# SCH_ipm_igbt_module_2025-05-30.net
KiCad netlist of a schematic drawn in EasyEDA
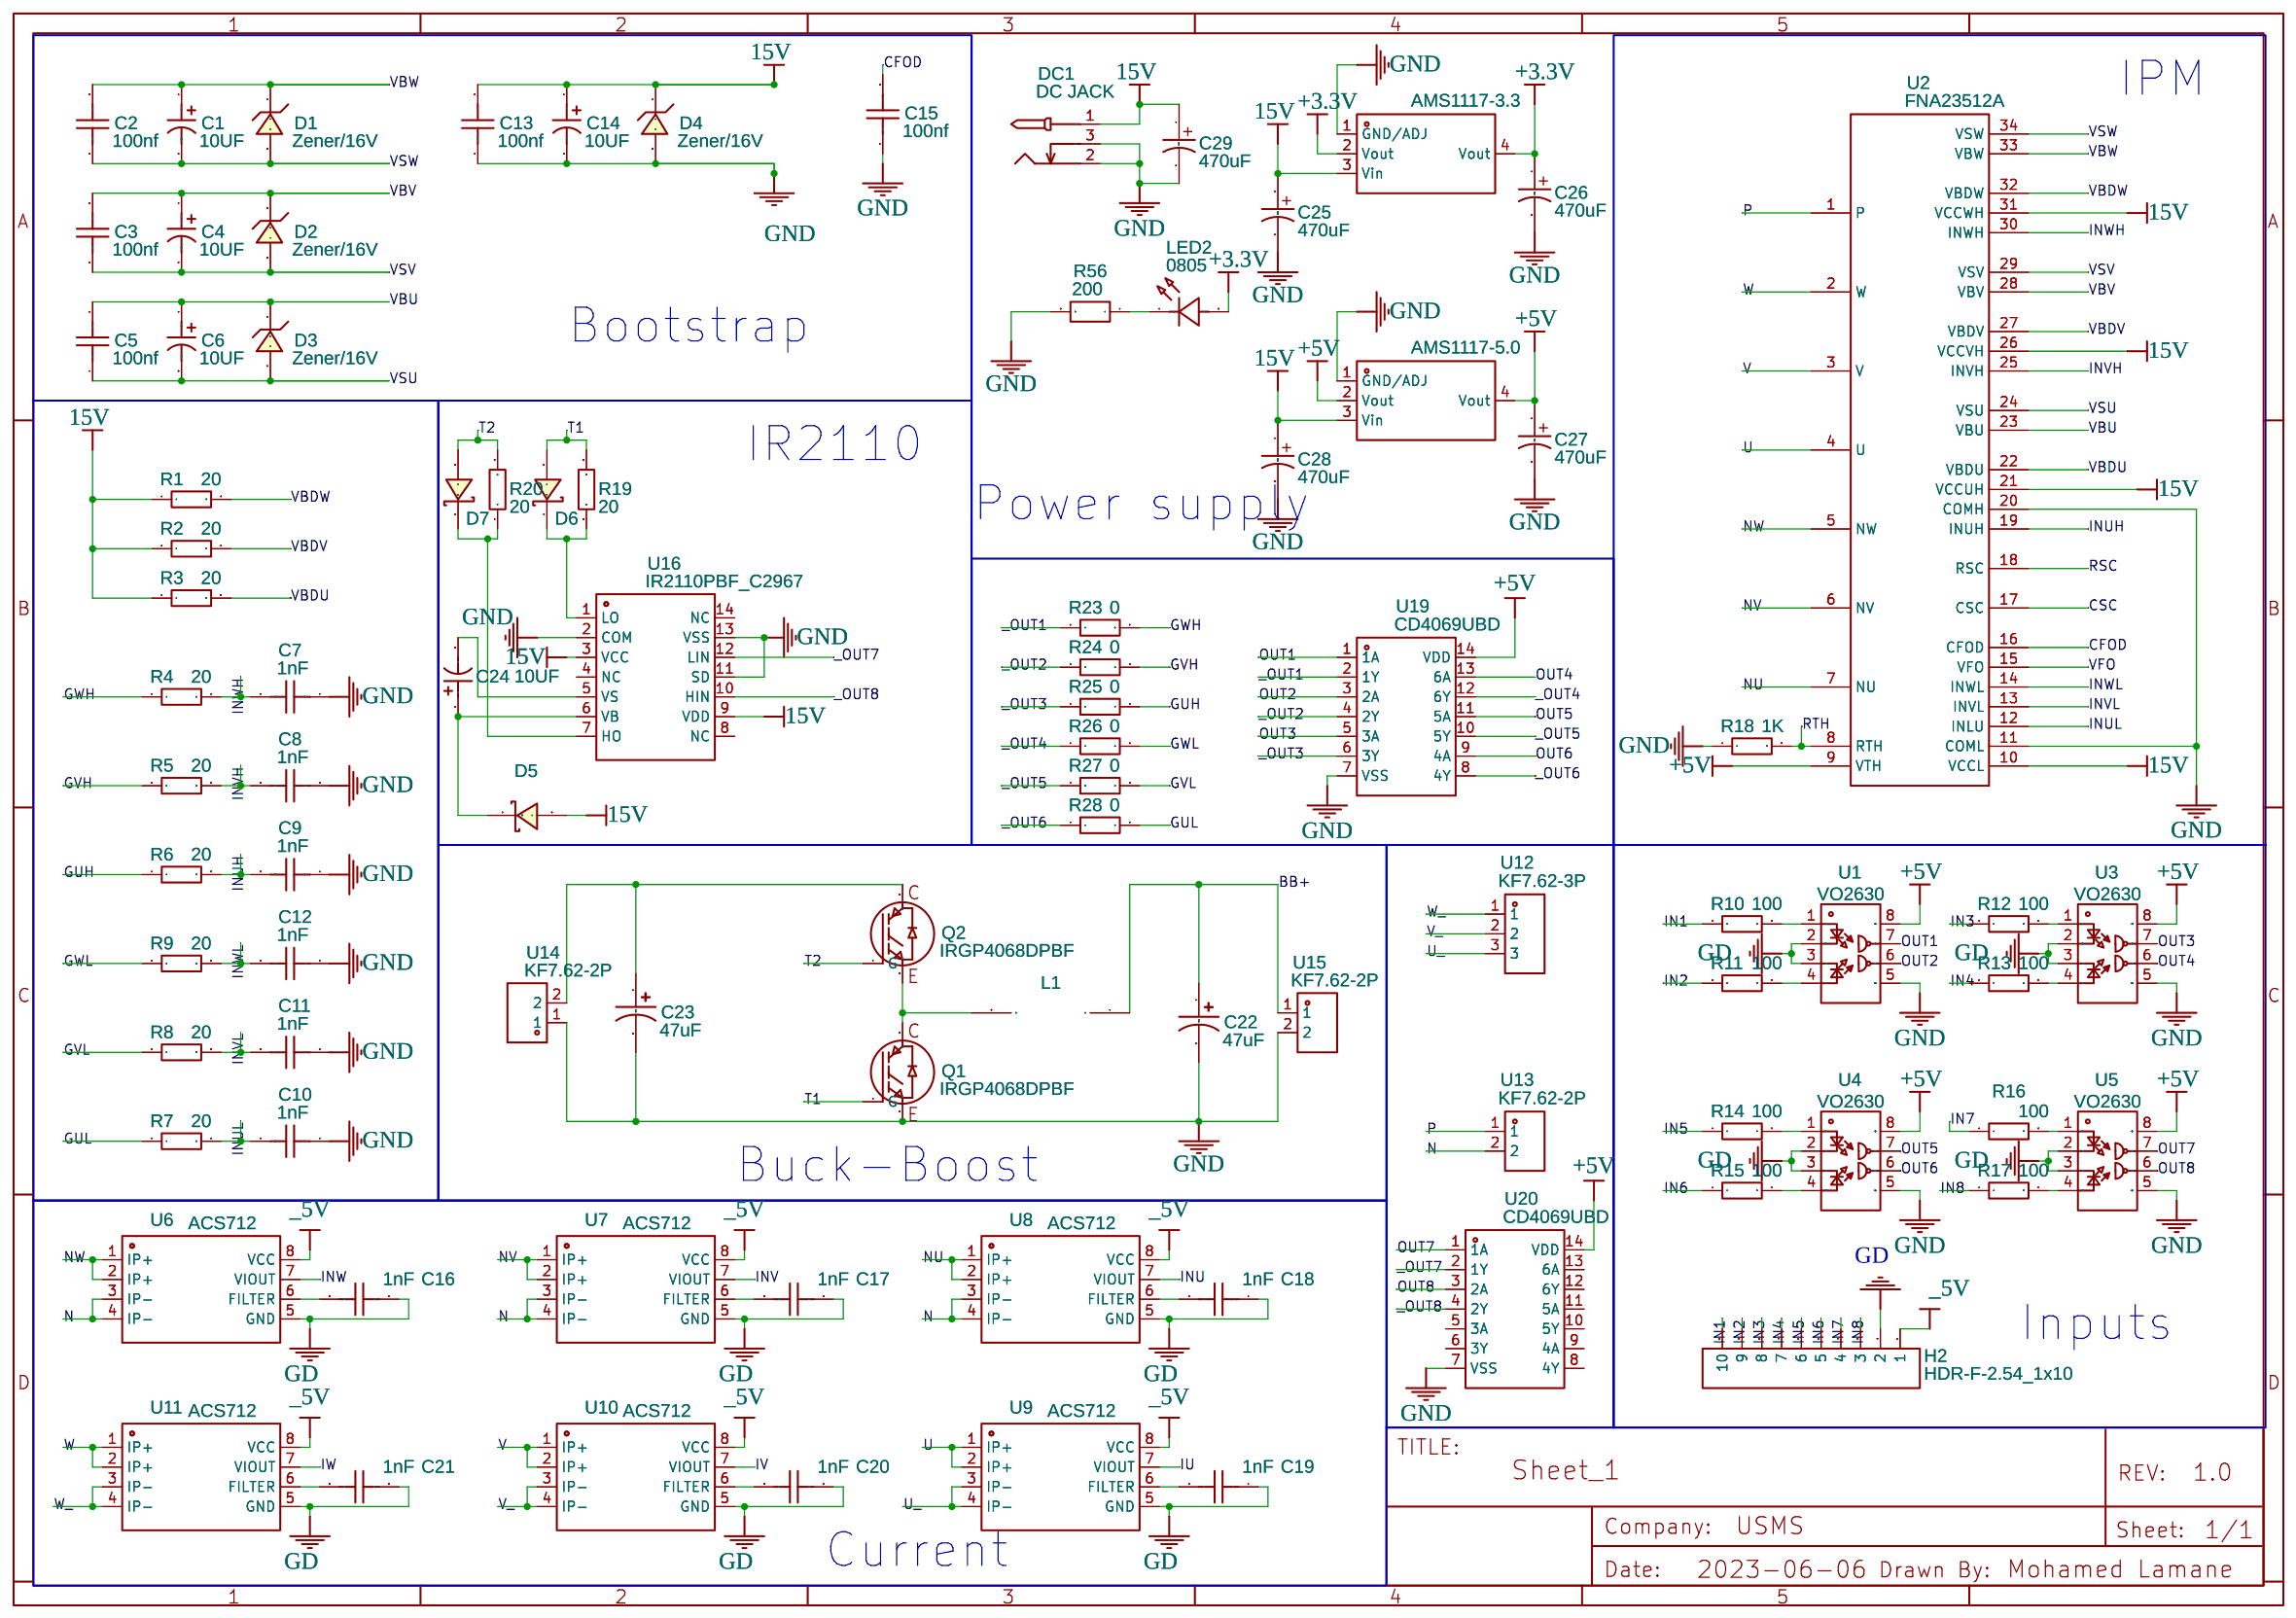
[diagram p0: Sheet_1]
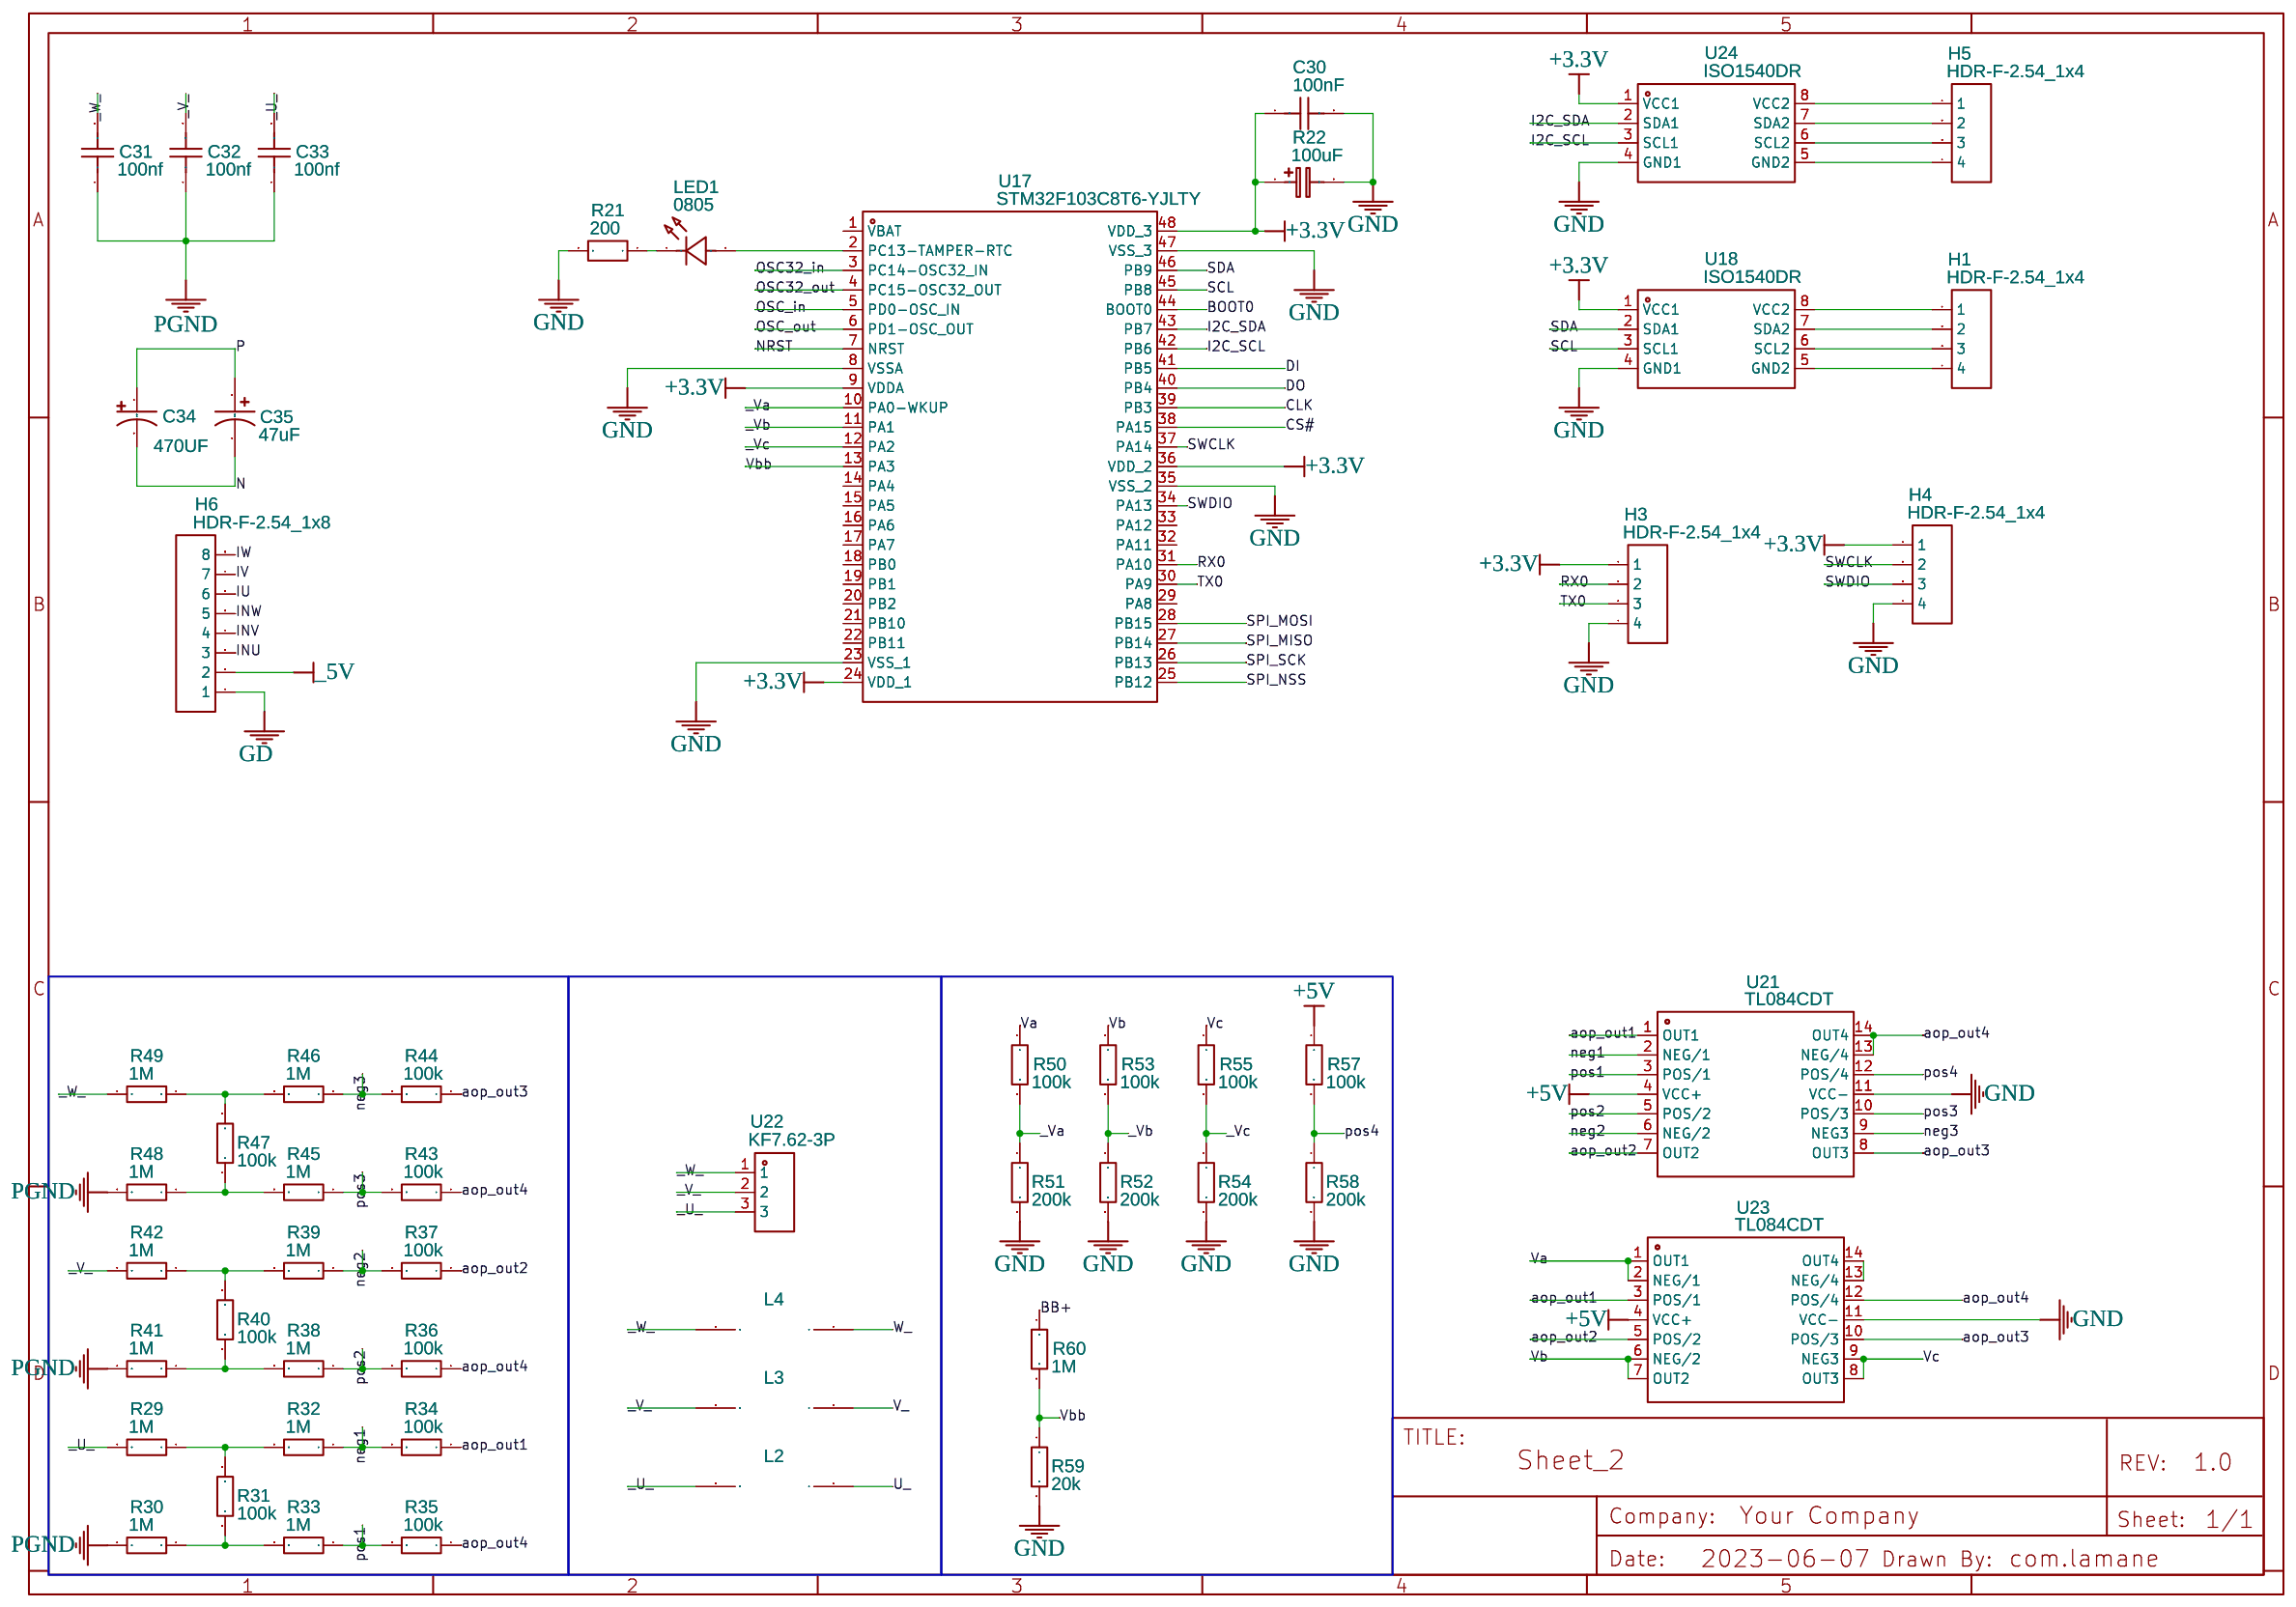
[diagram p1: Sheet_2]

(export (version "E")
  (design (tool "Eeschema 10.0.6"))
  (components
    (comp (ref "C1")
      (value "10UF")
      (fields (field (name "Manufacturer Part") "10uF/25V-C5X11DIP"))
      (libsource (lib "") (part "10UF/25V-C5X11DIP"))
    )
    (comp (ref "C2")
      (value "100nf")
      (fields (field (name "Manufacturer Part") "AC0805KKX7R9BB474"))
      (libsource (lib "") (part "AC0805KKX7R9BB474_1"))
    )
    (comp (ref "C3")
      (value "100nf")
      (fields (field (name "Manufacturer Part") "AC0805KKX7R9BB474"))
      (libsource (lib "") (part "AC0805KKX7R9BB474_1"))
    )
    (comp (ref "C4")
      (value "10UF")
      (fields (field (name "Manufacturer Part") "10uF/25V-C5X11DIP"))
      (libsource (lib "") (part "10UF/25V-C5X11DIP"))
    )
    (comp (ref "C5")
      (value "100nf")
      (fields (field (name "Manufacturer Part") "AC0805KKX7R9BB474"))
      (libsource (lib "") (part "AC0805KKX7R9BB474_1"))
    )
    (comp (ref "C6")
      (value "10UF")
      (fields (field (name "Manufacturer Part") "10uF/25V-C5X11DIP"))
      (libsource (lib "") (part "10UF/25V-C5X11DIP"))
    )
    (comp (ref "C7")
      (value "1nF")
      (fields (field (name "Manufacturer Part") "AC0805KKX7R9BB474"))
      (libsource (lib "") (part "AC0805KKX7R9BB474"))
    )
    (comp (ref "C8")
      (value "1nF")
      (fields (field (name "Manufacturer Part") "AC0805KKX7R9BB474"))
      (libsource (lib "") (part "AC0805KKX7R9BB474"))
    )
    (comp (ref "C9")
      (value "1nF")
      (fields (field (name "Manufacturer Part") "AC0805KKX7R9BB474"))
      (libsource (lib "") (part "AC0805KKX7R9BB474"))
    )
    (comp (ref "C10")
      (value "1nF")
      (fields (field (name "Manufacturer Part") "AC0805KKX7R9BB474"))
      (libsource (lib "") (part "AC0805KKX7R9BB474"))
    )
    (comp (ref "C11")
      (value "1nF")
      (fields (field (name "Manufacturer Part") "AC0805KKX7R9BB474"))
      (libsource (lib "") (part "AC0805KKX7R9BB474"))
    )
    (comp (ref "C12")
      (value "1nF")
      (fields (field (name "Manufacturer Part") "AC0805KKX7R9BB474"))
      (libsource (lib "") (part "AC0805KKX7R9BB474"))
    )
    (comp (ref "C13")
      (value "100nf")
      (fields (field (name "Manufacturer Part") "AC0805KKX7R9BB474"))
      (libsource (lib "") (part "AC0805KKX7R9BB474_1"))
    )
    (comp (ref "C14")
      (value "10UF")
      (fields (field (name "Manufacturer Part") "10uF/25V-C5X11DIP"))
      (libsource (lib "") (part "10UF/25V-C5X11DIP_1"))
    )
    (comp (ref "C15")
      (value "100nf")
      (fields (field (name "Manufacturer Part") "AC0805KKX7R9BB474"))
      (libsource (lib "") (part "AC0805KKX7R9BB474_1"))
    )
    (comp (ref "C16")
      (value "1nF")
      (fields (field (name "Manufacturer Part") "AC0805KKX7R9BB474"))
      (libsource (lib "") (part "AC0805KKX7R9BB474"))
    )
    (comp (ref "C17")
      (value "1nF")
      (fields (field (name "Manufacturer Part") "AC0805KKX7R9BB474"))
      (libsource (lib "") (part "AC0805KKX7R9BB474"))
    )
    (comp (ref "C18")
      (value "1nF")
      (fields (field (name "Manufacturer Part") "AC0805KKX7R9BB474"))
      (libsource (lib "") (part "AC0805KKX7R9BB474"))
    )
    (comp (ref "C19")
      (value "1nF")
      (fields (field (name "Manufacturer Part") "AC0805KKX7R9BB474"))
      (libsource (lib "") (part "AC0805KKX7R9BB474"))
    )
    (comp (ref "C20")
      (value "1nF")
      (fields (field (name "Manufacturer Part") "AC0805KKX7R9BB474"))
      (libsource (lib "") (part "AC0805KKX7R9BB474"))
    )
    (comp (ref "C21")
      (value "1nF")
      (fields (field (name "Manufacturer Part") "AC0805KKX7R9BB474"))
      (libsource (lib "") (part "AC0805KKX7R9BB474"))
    )
    (comp (ref "C22")
      (value "47uF")
      (fields (field (name "Manufacturer Part") "ECG2GM470L26OTBO") (field (name "Manufacturer") "Yunxing"))
      (libsource (lib "") (part "ECG2GM470L26OTBO"))
    )
    (comp (ref "C23")
      (value "47uF")
      (fields (field (name "Manufacturer Part") "ECG2GM470L26OTBO") (field (name "Manufacturer") "Yunxing"))
      (libsource (lib "") (part "ECG2GM470L26OTBO"))
    )
    (comp (ref "C24")
      (value "10UF")
      (fields (field (name "Manufacturer Part") "10uF/25V-C5X11DIP"))
      (libsource (lib "") (part "10UF/25V-C5X11DIP_2"))
    )
    (comp (ref "C25")
      (value "470uF")
      (fields (field (name "Manufacturer Part") "EEEFK1A471GP") (field (name "Manufacturer") "PANASONIC"))
      (libsource (lib "") (part "EEEFK1A471GP"))
    )
    (comp (ref "C26")
      (value "470uF")
      (fields (field (name "Manufacturer Part") "EEEFK1A471GP") (field (name "Manufacturer") "PANASONIC"))
      (libsource (lib "") (part "EEEFK1A471GP"))
    )
    (comp (ref "C27")
      (value "470uF")
      (fields (field (name "Manufacturer Part") "EEEFK1A471GP") (field (name "Manufacturer") "PANASONIC"))
      (libsource (lib "") (part "EEEFK1A471GP"))
    )
    (comp (ref "C28")
      (value "470uF")
      (fields (field (name "Manufacturer Part") "EEEFK1A471GP") (field (name "Manufacturer") "PANASONIC"))
      (libsource (lib "") (part "EEEFK1A471GP"))
    )
    (comp (ref "C29")
      (value "470uF")
      (fields (field (name "Manufacturer Part") "EEEFK1A471GP") (field (name "Manufacturer") "PANASONIC"))
      (libsource (lib "") (part "EEEFK1A471GP"))
    )
    (comp (ref "D1")
      (value "Zener/16V")
      (fields (field (name "Manufacturer Part") "MM3Z10VST1G") (field (name "Manufacturer") "onsemi(安森美)"))
      (libsource (lib "") (part "MM3Z10VST1G"))
    )
    (comp (ref "D2")
      (value "Zener/16V")
      (fields (field (name "Manufacturer Part") "MM3Z10VST1G") (field (name "Manufacturer") "onsemi(安森美)"))
      (libsource (lib "") (part "MM3Z10VST1G"))
    )
    (comp (ref "D3")
      (value "Zener/16V")
      (fields (field (name "Manufacturer Part") "MM3Z10VST1G") (field (name "Manufacturer") "onsemi(安森美)"))
      (libsource (lib "") (part "MM3Z10VST1G"))
    )
    (comp (ref "D4")
      (value "Zener/16V")
      (fields (field (name "Manufacturer Part") "MM3Z10VST1G") (field (name "Manufacturer") "onsemi(安森美)"))
      (libsource (lib "") (part "MM3Z10VST1G"))
    )
    (comp (ref "D5") (value "SODFL250X10-2N") (libsource (lib "") (part "SODFL250X10-2N_1")))
    (comp (ref "D6") (value "SODFL250X10-2N") (libsource (lib "") (part "SODFL250X10-2N")))
    (comp (ref "D7") (value "SODFL250X10-2N") (libsource (lib "") (part "SODFL250X10-2N")))
    (comp (ref "DC1")
      (value "DC JACK")
      (fields (field (name "Manufacturer Part") "DC005-2.0MM") (field (name "Manufacturer") "SOFNG"))
      (libsource (lib "") (part "DC JACK"))
    )
    (comp (ref "H2") (value "HDR-F-2.54_1x10") (libsource (lib "") (part "HDR-F-2.54_1x10")))
    (comp (ref "L1") (value "indu") (libsource (lib "") (part "indu")))
    (comp (ref "LED2")
      (value "0805")
      (fields (field (name "Manufacturer Part") "D21121000251-LED0805_R"))
      (libsource (lib "") (part "D21121000251-LED0805_R"))
    )
    (comp (ref "NO1")
      (value "AMS1117-3.3")
      (fields (field (name "Manufacturer Part") "AMS1117-3.3-YJLTY"))
      (libsource (lib "") (part "AMS1117-3.3-YJLTY"))
    )
    (comp (ref "NO2")
      (value "AMS1117-5.0")
      (fields (field (name "Manufacturer Part") "AMS1117-3.3-YJLTY"))
      (libsource (lib "") (part "AMS1117-3.3-YJLTY"))
    )
    (comp (ref "Q1")
      (value "IRGP4068DPBF")
      (fields (field (name "Manufacturer") "IR"))
      (libsource (lib "") (part "IRGP4068DPBF"))
    )
    (comp (ref "Q2")
      (value "IRGP4068DPBF")
      (fields (field (name "Manufacturer") "IR"))
      (libsource (lib "") (part "IRGP4068DPBF"))
    )
    (comp (ref "R1")
      (value "20")
      (fields (field (name "Manufacturer Part") "8K1%-R0603"))
      (libsource (lib "") (part "8K1%-R0603"))
    )
    (comp (ref "R2")
      (value "20")
      (fields (field (name "Manufacturer Part") "8K1%-R0603"))
      (libsource (lib "") (part "8K1%-R0603"))
    )
    (comp (ref "R3")
      (value "20")
      (fields (field (name "Manufacturer Part") "8K1%-R0603"))
      (libsource (lib "") (part "8K1%-R0603"))
    )
    (comp (ref "R4")
      (value "20")
      (fields (field (name "Manufacturer Part") "8K1%-R0603"))
      (libsource (lib "") (part "8K1%-R0603"))
    )
    (comp (ref "R5")
      (value "20")
      (fields (field (name "Manufacturer Part") "8K1%-R0603"))
      (libsource (lib "") (part "8K1%-R0603"))
    )
    (comp (ref "R6")
      (value "20")
      (fields (field (name "Manufacturer Part") "8K1%-R0603"))
      (libsource (lib "") (part "8K1%-R0603"))
    )
    (comp (ref "R7")
      (value "20")
      (fields (field (name "Manufacturer Part") "8K1%-R0603"))
      (libsource (lib "") (part "8K1%-R0603"))
    )
    (comp (ref "R8")
      (value "20")
      (fields (field (name "Manufacturer Part") "8K1%-R0603"))
      (libsource (lib "") (part "8K1%-R0603"))
    )
    (comp (ref "R9")
      (value "20")
      (fields (field (name "Manufacturer Part") "8K1%-R0603"))
      (libsource (lib "") (part "8K1%-R0603"))
    )
    (comp (ref "R10")
      (value "100")
      (fields (field (name "Manufacturer Part") "8K1%-R0603"))
      (libsource (lib "") (part "8K1%-R0603"))
    )
    (comp (ref "R11")
      (value "100")
      (fields (field (name "Manufacturer Part") "8K1%-R0603"))
      (libsource (lib "") (part "8K1%-R0603"))
    )
    (comp (ref "R12")
      (value "100")
      (fields (field (name "Manufacturer Part") "8K1%-R0603"))
      (libsource (lib "") (part "8K1%-R0603"))
    )
    (comp (ref "R13")
      (value "100")
      (fields (field (name "Manufacturer Part") "8K1%-R0603"))
      (libsource (lib "") (part "8K1%-R0603"))
    )
    (comp (ref "R14")
      (value "100")
      (fields (field (name "Manufacturer Part") "8K1%-R0603"))
      (libsource (lib "") (part "8K1%-R0603"))
    )
    (comp (ref "R15")
      (value "100")
      (fields (field (name "Manufacturer Part") "8K1%-R0603"))
      (libsource (lib "") (part "8K1%-R0603"))
    )
    (comp (ref "R16")
      (value "100")
      (fields (field (name "Manufacturer Part") "8K1%-R0603"))
      (libsource (lib "") (part "8K1%-R0603"))
    )
    (comp (ref "R17")
      (value "100")
      (fields (field (name "Manufacturer Part") "8K1%-R0603"))
      (libsource (lib "") (part "8K1%-R0603"))
    )
    (comp (ref "R18")
      (value "1K")
      (fields (field (name "Manufacturer Part") "8K1%-R0603"))
      (libsource (lib "") (part "8K1%-R0603"))
    )
    (comp (ref "R19")
      (value "20")
      (fields (field (name "Manufacturer Part") "8K1%-R0603"))
      (libsource (lib "") (part "8K1%-R0603_1"))
    )
    (comp (ref "R20")
      (value "20")
      (fields (field (name "Manufacturer Part") "8K1%-R0603"))
      (libsource (lib "") (part "8K1%-R0603_1"))
    )
    (comp (ref "R23")
      (value "0")
      (fields (field (name "Manufacturer Part") "8K1%-R0603"))
      (libsource (lib "") (part "8K1%-R0603"))
    )
    (comp (ref "R24")
      (value "0")
      (fields (field (name "Manufacturer Part") "8K1%-R0603"))
      (libsource (lib "") (part "8K1%-R0603"))
    )
    (comp (ref "R25")
      (value "0")
      (fields (field (name "Manufacturer Part") "8K1%-R0603"))
      (libsource (lib "") (part "8K1%-R0603"))
    )
    (comp (ref "R26")
      (value "0")
      (fields (field (name "Manufacturer Part") "8K1%-R0603"))
      (libsource (lib "") (part "8K1%-R0603"))
    )
    (comp (ref "R27")
      (value "0")
      (fields (field (name "Manufacturer Part") "8K1%-R0603"))
      (libsource (lib "") (part "8K1%-R0603"))
    )
    (comp (ref "R28")
      (value "0")
      (fields (field (name "Manufacturer Part") "8K1%-R0603"))
      (libsource (lib "") (part "8K1%-R0603"))
    )
    (comp (ref "R56")
      (value "200")
      (fields (field (name "Manufacturer Part") "PTFR0805B9K10P9") (field (name "Manufacturer") "RESI(开步睿思）"))
      (libsource (lib "") (part "PTFR0805B9K10P9"))
    )
    (comp (ref "U1")
      (value "VO2630")
      (fields (field (name "Manufacturer Part") "VO2630-X007T") (field (name "Manufacturer") "VISHAY(威世)"))
      (libsource (lib "") (part "VO2630-X007T"))
    )
    (comp (ref "U2")
      (value "FNA23512A")
      (fields (field (name "Manufacturer") "ON(安森美)"))
      (libsource (lib "") (part "FNA23512A"))
    )
    (comp (ref "U3")
      (value "VO2630")
      (fields (field (name "Manufacturer Part") "VO2630-X007T") (field (name "Manufacturer") "VISHAY(威世)"))
      (libsource (lib "") (part "VO2630-X007T"))
    )
    (comp (ref "U4")
      (value "VO2630")
      (fields (field (name "Manufacturer Part") "VO2630-X007T") (field (name "Manufacturer") "VISHAY(威世)"))
      (libsource (lib "") (part "VO2630-X007T"))
    )
    (comp (ref "U5")
      (value "VO2630")
      (fields (field (name "Manufacturer Part") "VO2630-X007T") (field (name "Manufacturer") "VISHAY(威世)"))
      (libsource (lib "") (part "VO2630-X007T"))
    )
    (comp (ref "U6")
      (value "ACS712")
      (fields
        (field (name "Manufacturer Part") "ACS712ELCTR-30A-T")
        (field (name "Manufacturer") "ALLEGRO(美国埃戈罗)")
      )
      (libsource (lib "") (part "ACS712ELCTR-30A-T"))
    )
    (comp (ref "U7")
      (value "ACS712")
      (fields
        (field (name "Manufacturer Part") "ACS712ELCTR-30A-T")
        (field (name "Manufacturer") "ALLEGRO(美国埃戈罗)")
      )
      (libsource (lib "") (part "ACS712ELCTR-30A-T"))
    )
    (comp (ref "U8")
      (value "ACS712")
      (fields
        (field (name "Manufacturer Part") "ACS712ELCTR-30A-T")
        (field (name "Manufacturer") "ALLEGRO(美国埃戈罗)")
      )
      (libsource (lib "") (part "ACS712ELCTR-30A-T"))
    )
    (comp (ref "U9")
      (value "ACS712")
      (fields
        (field (name "Manufacturer Part") "ACS712ELCTR-30A-T")
        (field (name "Manufacturer") "ALLEGRO(美国埃戈罗)")
      )
      (libsource (lib "") (part "ACS712ELCTR-30A-T"))
    )
    (comp (ref "U10")
      (value "ACS712")
      (fields
        (field (name "Manufacturer Part") "ACS712ELCTR-30A-T")
        (field (name "Manufacturer") "ALLEGRO(美国埃戈罗)")
      )
      (libsource (lib "") (part "ACS712ELCTR-30A-T"))
    )
    (comp (ref "U11")
      (value "ACS712")
      (fields
        (field (name "Manufacturer Part") "ACS712ELCTR-30A-T")
        (field (name "Manufacturer") "ALLEGRO(美国埃戈罗)")
      )
      (libsource (lib "") (part "ACS712ELCTR-30A-T"))
    )
    (comp (ref "U12")
      (value "KF7.62-3P")
      (fields (field (name "Manufacturer") "KEFA(科发)"))
      (libsource (lib "") (part "KF7.62-3P"))
    )
    (comp (ref "U13")
      (value "KF7.62-2P")
      (fields (field (name "Manufacturer") "KEFA(科发)"))
      (libsource (lib "") (part "KF7.62-2P"))
    )
    (comp (ref "U14")
      (value "KF7.62-2P")
      (fields (field (name "Manufacturer") "KEFA(科发)"))
      (libsource (lib "") (part "KF7.62-2P_1"))
    )
    (comp (ref "U15")
      (value "KF7.62-2P")
      (fields (field (name "Manufacturer") "KEFA(科发)"))
      (libsource (lib "") (part "KF7.62-2P"))
    )
    (comp (ref "U16")
      (value "IR2110PBF_C2967")
      (fields (field (name "Manufacturer Part") "IR2110PBF") (field (name "Manufacturer") "Infineon(英飞凌)"))
      (libsource (lib "") (part "IR2110PBF_C2967"))
    )
    (comp (ref "U19")
      (value "CD4069UBD")
      (fields (field (name "Manufacturer") "HTC"))
      (libsource (lib "") (part "CD4069UBD"))
    )
    (comp (ref "U20")
      (value "CD4069UBD")
      (fields (field (name "Manufacturer") "HTC"))
      (libsource (lib "") (part "CD4069UBD"))
    )
    (comp (ref "C30")
      (value "100nF")
      (fields (field (name "Manufacturer Part") "GRM216R71H103KA01D") (field (name "Manufacturer") "MuRata"))
      (libsource (lib "") (part "GRM216R71H103KA01D"))
    )
    (comp (ref "C31")
      (value "100nf")
      (fields
        (field (name "Manufacturer Part") "1uf/250V/CBBCapacitor")
        (field (name "Manufacturer") "ReliaPro")
      )
      (libsource (lib "") (part "1uf/250V/CBBCapacitor"))
    )
    (comp (ref "C32")
      (value "100nf")
      (fields
        (field (name "Manufacturer Part") "1uf/250V/CBBCapacitor")
        (field (name "Manufacturer") "ReliaPro")
      )
      (libsource (lib "") (part "1uf/250V/CBBCapacitor"))
    )
    (comp (ref "C33")
      (value "100nf")
      (fields
        (field (name "Manufacturer Part") "1uf/250V/CBBCapacitor")
        (field (name "Manufacturer") "ReliaPro")
      )
      (libsource (lib "") (part "1uf/250V/CBBCapacitor"))
    )
    (comp (ref "C34") (value "470UF") (libsource (lib "") (part "407UF/400V")))
    (comp (ref "C35")
      (value "47uF")
      (fields (field (name "Manufacturer Part") "ECG2GM470L26OTBO") (field (name "Manufacturer") "Yunxing"))
      (libsource (lib "") (part "ECG2GM470L26OTBO"))
    )
    (comp (ref "H1") (value "HDR-F-2.54_1x4") (libsource (lib "") (part "HDR-F-2.54_1x4")))
    (comp (ref "H3") (value "HDR-F-2.54_1x4") (libsource (lib "") (part "HDR-F-2.54_1x4")))
    (comp (ref "H4") (value "HDR-F-2.54_1x4") (libsource (lib "") (part "HDR-F-2.54_1x4")))
    (comp (ref "H5") (value "HDR-F-2.54_1x4") (libsource (lib "") (part "HDR-F-2.54_1x4")))
    (comp (ref "H6") (value "HDR-F-2.54_1x8") (libsource (lib "") (part "HDR-F-2.54_1x8")))
    (comp (ref "L2") (value "indu") (libsource (lib "") (part "indu")))
    (comp (ref "L3") (value "indu") (libsource (lib "") (part "indu")))
    (comp (ref "L4") (value "indu") (libsource (lib "") (part "indu")))
    (comp (ref "LED1")
      (value "0805")
      (fields (field (name "Manufacturer Part") "D21121000251-LED0805_R"))
      (libsource (lib "") (part "D21121000251-LED0805_R"))
    )
    (comp (ref "R21")
      (value "200")
      (fields (field (name "Manufacturer Part") "PTFR0805B9K10P9") (field (name "Manufacturer") "RESI(开步睿思）"))
      (libsource (lib "") (part "PTFR0805B9K10P9"))
    )
    (comp (ref "R22")
      (value "100uF")
      (fields
        (field (name "Manufacturer Part") "T520A107M006ATE045")
        (field (name "Manufacturer") "KEMET(基美)")
      )
      (libsource (lib "") (part "T520A107M006ATE045"))
    )
    (comp (ref "R29")
      (value "1M")
      (fields (field (name "Manufacturer Part") "8K1%-R0603"))
      (libsource (lib "") (part "8K1%-R0603"))
    )
    (comp (ref "R30")
      (value "1M")
      (fields (field (name "Manufacturer Part") "8K1%-R0603"))
      (libsource (lib "") (part "8K1%-R0603"))
    )
    (comp (ref "R31")
      (value "100k")
      (fields (field (name "Manufacturer Part") "8K1%-R0603"))
      (libsource (lib "") (part "8K1%-R0603_2"))
    )
    (comp (ref "R32")
      (value "1M")
      (fields (field (name "Manufacturer Part") "8K1%-R0603"))
      (libsource (lib "") (part "8K1%-R0603"))
    )
    (comp (ref "R33")
      (value "1M")
      (fields (field (name "Manufacturer Part") "8K1%-R0603"))
      (libsource (lib "") (part "8K1%-R0603"))
    )
    (comp (ref "R34")
      (value "100k")
      (fields (field (name "Manufacturer Part") "8K1%-R0603"))
      (libsource (lib "") (part "8K1%-R0603"))
    )
    (comp (ref "R35")
      (value "100k")
      (fields (field (name "Manufacturer Part") "8K1%-R0603"))
      (libsource (lib "") (part "8K1%-R0603"))
    )
    (comp (ref "R36")
      (value "100k")
      (fields (field (name "Manufacturer Part") "8K1%-R0603"))
      (libsource (lib "") (part "8K1%-R0603"))
    )
    (comp (ref "R37")
      (value "100k")
      (fields (field (name "Manufacturer Part") "8K1%-R0603"))
      (libsource (lib "") (part "8K1%-R0603"))
    )
    (comp (ref "R38")
      (value "1M")
      (fields (field (name "Manufacturer Part") "8K1%-R0603"))
      (libsource (lib "") (part "8K1%-R0603"))
    )
    (comp (ref "R39")
      (value "1M")
      (fields (field (name "Manufacturer Part") "8K1%-R0603"))
      (libsource (lib "") (part "8K1%-R0603"))
    )
    (comp (ref "R40")
      (value "100k")
      (fields (field (name "Manufacturer Part") "8K1%-R0603"))
      (libsource (lib "") (part "8K1%-R0603_2"))
    )
    (comp (ref "R41")
      (value "1M")
      (fields (field (name "Manufacturer Part") "8K1%-R0603"))
      (libsource (lib "") (part "8K1%-R0603"))
    )
    (comp (ref "R42")
      (value "1M")
      (fields (field (name "Manufacturer Part") "8K1%-R0603"))
      (libsource (lib "") (part "8K1%-R0603"))
    )
    (comp (ref "R43")
      (value "100k")
      (fields (field (name "Manufacturer Part") "8K1%-R0603"))
      (libsource (lib "") (part "8K1%-R0603"))
    )
    (comp (ref "R44")
      (value "100k")
      (fields (field (name "Manufacturer Part") "8K1%-R0603"))
      (libsource (lib "") (part "8K1%-R0603"))
    )
    (comp (ref "R45")
      (value "1M")
      (fields (field (name "Manufacturer Part") "8K1%-R0603"))
      (libsource (lib "") (part "8K1%-R0603"))
    )
    (comp (ref "R46")
      (value "1M")
      (fields (field (name "Manufacturer Part") "8K1%-R0603"))
      (libsource (lib "") (part "8K1%-R0603"))
    )
    (comp (ref "R47")
      (value "100k")
      (fields (field (name "Manufacturer Part") "8K1%-R0603"))
      (libsource (lib "") (part "8K1%-R0603_2"))
    )
    (comp (ref "R48")
      (value "1M")
      (fields (field (name "Manufacturer Part") "8K1%-R0603"))
      (libsource (lib "") (part "8K1%-R0603"))
    )
    (comp (ref "R49")
      (value "1M")
      (fields (field (name "Manufacturer Part") "8K1%-R0603"))
      (libsource (lib "") (part "8K1%-R0603"))
    )
    (comp (ref "R50")
      (value "100k")
      (fields (field (name "Manufacturer Part") "8K1%-R0603"))
      (libsource (lib "") (part "8K1%-R0603_1"))
    )
    (comp (ref "R51")
      (value "200k")
      (fields (field (name "Manufacturer Part") "8K1%-R0603"))
      (libsource (lib "") (part "8K1%-R0603_1"))
    )
    (comp (ref "R52")
      (value "200k")
      (fields (field (name "Manufacturer Part") "8K1%-R0603"))
      (libsource (lib "") (part "8K1%-R0603_1"))
    )
    (comp (ref "R53")
      (value "100k")
      (fields (field (name "Manufacturer Part") "8K1%-R0603"))
      (libsource (lib "") (part "8K1%-R0603_1"))
    )
    (comp (ref "R54")
      (value "200k")
      (fields (field (name "Manufacturer Part") "8K1%-R0603"))
      (libsource (lib "") (part "8K1%-R0603_1"))
    )
    (comp (ref "R55")
      (value "100k")
      (fields (field (name "Manufacturer Part") "8K1%-R0603"))
      (libsource (lib "") (part "8K1%-R0603_1"))
    )
    (comp (ref "R57")
      (value "100k")
      (fields (field (name "Manufacturer Part") "8K1%-R0603"))
      (libsource (lib "") (part "8K1%-R0603_1"))
    )
    (comp (ref "R58")
      (value "200k")
      (fields (field (name "Manufacturer Part") "8K1%-R0603"))
      (libsource (lib "") (part "8K1%-R0603_1"))
    )
    (comp (ref "R59")
      (value "20k")
      (fields (field (name "Manufacturer Part") "8K1%-R0603"))
      (libsource (lib "") (part "8K1%-R0603_1"))
    )
    (comp (ref "R60")
      (value "1M")
      (fields (field (name "Manufacturer Part") "8K1%-R0603"))
      (libsource (lib "") (part "8K1%-R0603_1"))
    )
    (comp (ref "U17") (value "STM32F103C8T6-YJLTY") (libsource (lib "") (part "STM32F103C8T6-YJLTY")))
    (comp (ref "U18")
      (value "ISO1540DR")
      (fields (field (name "Manufacturer") "TI(德州仪器)"))
      (libsource (lib "") (part "ISO1540DR"))
    )
    (comp (ref "U21")
      (value "TL084CDT")
      (fields (field (name "Manufacturer") "ST(意法半导体)"))
      (libsource (lib "") (part "TL084CDT"))
    )
    (comp (ref "U22")
      (value "KF7.62-3P")
      (fields (field (name "Manufacturer") "KEFA(科发)"))
      (libsource (lib "") (part "KF7.62-3P"))
    )
    (comp (ref "U23")
      (value "TL084CDT")
      (fields (field (name "Manufacturer") "ST(意法半导体)"))
      (libsource (lib "") (part "TL084CDT"))
    )
    (comp (ref "U24")
      (value "ISO1540DR")
      (fields (field (name "Manufacturer") "TI(德州仪器)"))
      (libsource (lib "") (part "ISO1540DR"))
    )
  )
  (nets
    (net (code "1") (name "+3.3V") (class "Default")
      (node (ref "C26") (pin "1") (pinfunction "1_1") (pintype "unspecified"))
      (node (ref "C30") (pin "1") (pinfunction "1_1") (pintype "unspecified"))
      (node (ref "H3") (pin "1") (pinfunction "1_1") (pintype "unspecified"))
      (node (ref "H4") (pin "1") (pinfunction "1_1") (pintype "unspecified"))
      (node (ref "LED2") (pin "2") (pinfunction "A_2") (pintype "unspecified"))
      (node (ref "NO1") (pin "2") (pinfunction "Vout_2") (pintype "unspecified"))
      (node (ref "NO1") (pin "4") (pinfunction "Vout_4") (pintype "unspecified"))
      (node (ref "R22") (pin "1") (pinfunction "1_1") (pintype "unspecified"))
      (node (ref "U17") (pin "24") (pinfunction "VDD_1_24") (pintype "unspecified"))
      (node (ref "U17") (pin "36") (pinfunction "VDD_2_36") (pintype "unspecified"))
      (node (ref "U17") (pin "48") (pinfunction "VDD_3_48") (pintype "unspecified"))
      (node (ref "U17") (pin "9") (pinfunction "VDDA_9") (pintype "unspecified"))
      (node (ref "U18") (pin "1") (pinfunction "VCC1_1") (pintype "unspecified"))
      (node (ref "U24") (pin "1") (pinfunction "VCC1_1") (pintype "unspecified"))
    )
    (net (code "2") (name "+5V") (class "Default")
      (node (ref "C27") (pin "1") (pinfunction "1_1") (pintype "unspecified"))
      (node (ref "NO2") (pin "2") (pinfunction "Vout_2") (pintype "unspecified"))
      (node (ref "NO2") (pin "4") (pinfunction "Vout_4") (pintype "unspecified"))
      (node (ref "R57") (pin "1") (pinfunction "1_1") (pintype "unspecified"))
      (node (ref "U1") (pin "8") (pinfunction "VCC_8") (pintype "unspecified"))
      (node (ref "U19") (pin "14") (pinfunction "VDD_14") (pintype "unspecified"))
      (node (ref "U2") (pin "9") (pinfunction "VTH_9") (pintype "unspecified"))
      (node (ref "U20") (pin "14") (pinfunction "VDD_14") (pintype "unspecified"))
      (node (ref "U21") (pin "4") (pinfunction "VCC+_4") (pintype "unspecified"))
      (node (ref "U23") (pin "4") (pinfunction "VCC+_4") (pintype "unspecified"))
      (node (ref "U3") (pin "8") (pinfunction "VCC_8") (pintype "unspecified"))
      (node (ref "U4") (pin "8") (pinfunction "VCC_8") (pintype "unspecified"))
      (node (ref "U5") (pin "8") (pinfunction "VCC_8") (pintype "unspecified"))
    )
    (net (code "3") (name "15V") (class "Default")
      (node (ref "C13") (pin "2") (pinfunction "2_2") (pintype "unspecified"))
      (node (ref "C14") (pin "1") (pinfunction "1_1") (pintype "input"))
      (node (ref "C25") (pin "1") (pinfunction "1_1") (pintype "unspecified"))
      (node (ref "C28") (pin "1") (pinfunction "1_1") (pintype "unspecified"))
      (node (ref "C29") (pin "1") (pinfunction "1_1") (pintype "unspecified"))
      (node (ref "D4") (pin "1") (pinfunction "K_1") (pintype "unspecified"))
      (node (ref "D5") (pin "2") (pinfunction "A_2") (pintype "unspecified"))
      (node (ref "DC1") (pin "1") (pinfunction "1_1") (pintype "unspecified"))
      (node (ref "NO1") (pin "3") (pinfunction "Vin_3") (pintype "unspecified"))
      (node (ref "NO2") (pin "3") (pinfunction "Vin_3") (pintype "unspecified"))
      (node (ref "R1") (pin "1") (pinfunction "1_1") (pintype "unspecified"))
      (node (ref "R2") (pin "1") (pinfunction "1_1") (pintype "unspecified"))
      (node (ref "R3") (pin "1") (pinfunction "1_1") (pintype "unspecified"))
      (node (ref "U16") (pin "3") (pinfunction "VCC_3") (pintype "unspecified"))
      (node (ref "U16") (pin "9") (pinfunction "VDD_9") (pintype "unspecified"))
      (node (ref "U2") (pin "10") (pinfunction "VCCL_10") (pintype "unspecified"))
      (node (ref "U2") (pin "21") (pinfunction "VCCUH_21") (pintype "unspecified"))
      (node (ref "U2") (pin "26") (pinfunction "VCCVH_26") (pintype "unspecified"))
      (node (ref "U2") (pin "31") (pinfunction "VCCWH_31") (pintype "unspecified"))
    )
    (net (code "4") (name "BB+") (class "Default")
      (node (ref "C22") (pin "1") (pinfunction "1_1") (pintype "unspecified"))
      (node (ref "L1") (pin "1") (pinfunction "1_1") (pintype "unspecified"))
      (node (ref "R60") (pin "1") (pinfunction "1_1") (pintype "unspecified"))
      (node (ref "U15") (pin "1") (pinfunction "1_1") (pintype "unspecified"))
    )
    (net (code "5") (name "BOOT0") (class "Default")
      (node (ref "U17") (pin "44") (pinfunction "BOOT0_44") (pintype "unspecified"))
    )
    (net (code "6") (name "CFOD") (class "Default")
      (node (ref "C15") (pin "2") (pinfunction "2_2") (pintype "unspecified"))
      (node (ref "U2") (pin "16") (pinfunction "CFOD_16") (pintype "unspecified"))
    )
    (net (code "7") (name "CLK") (class "Default")
      (node (ref "U17") (pin "39") (pinfunction "PB3_39") (pintype "unspecified"))
    )
    (net (code "8") (name "CS#") (class "Default")
      (node (ref "U17") (pin "38") (pinfunction "PA15_38") (pintype "unspecified"))
    )
    (net (code "9") (name "CSC") (class "Default")
      (node (ref "U2") (pin "17") (pinfunction "CSC_17") (pintype "unspecified"))
    )
    (net (code "10") (name "DI") (class "Default")
      (node (ref "U17") (pin "41") (pinfunction "PB5_41") (pintype "unspecified"))
    )
    (net (code "11") (name "DO") (class "Default")
      (node (ref "U17") (pin "40") (pinfunction "PB4_40") (pintype "unspecified"))
    )
    (net (code "12") (name "GD") (class "Default")
      (node (ref "C16") (pin "1") (pinfunction "1_1") (pintype "unspecified"))
      (node (ref "C17") (pin "1") (pinfunction "1_1") (pintype "unspecified"))
      (node (ref "C18") (pin "1") (pinfunction "1_1") (pintype "unspecified"))
      (node (ref "C19") (pin "1") (pinfunction "1_1") (pintype "unspecified"))
      (node (ref "C20") (pin "1") (pinfunction "1_1") (pintype "unspecified"))
      (node (ref "C21") (pin "1") (pinfunction "1_1") (pintype "unspecified"))
      (node (ref "H2") (pin "2") (pinfunction "2_2") (pintype "unspecified"))
      (node (ref "H6") (pin "1") (pinfunction "1_1") (pintype "unspecified"))
      (node (ref "U1") (pin "2") (pinfunction "C1_2") (pintype "unspecified"))
      (node (ref "U1") (pin "3") (pinfunction "C2_3") (pintype "unspecified"))
      (node (ref "U10") (pin "5") (pinfunction "GND_5") (pintype "unspecified"))
      (node (ref "U11") (pin "5") (pinfunction "GND_5") (pintype "unspecified"))
      (node (ref "U3") (pin "2") (pinfunction "C1_2") (pintype "unspecified"))
      (node (ref "U3") (pin "3") (pinfunction "C2_3") (pintype "unspecified"))
      (node (ref "U4") (pin "2") (pinfunction "C1_2") (pintype "unspecified"))
      (node (ref "U4") (pin "3") (pinfunction "C2_3") (pintype "unspecified"))
      (node (ref "U5") (pin "2") (pinfunction "C1_2") (pintype "unspecified"))
      (node (ref "U5") (pin "3") (pinfunction "C2_3") (pintype "unspecified"))
      (node (ref "U6") (pin "5") (pinfunction "GND_5") (pintype "unspecified"))
      (node (ref "U7") (pin "5") (pinfunction "GND_5") (pintype "unspecified"))
      (node (ref "U8") (pin "5") (pinfunction "GND_5") (pintype "unspecified"))
      (node (ref "U9") (pin "5") (pinfunction "GND_5") (pintype "unspecified"))
    )
    (net (code "13") (name "GND") (class "Default")
      (node (ref "C10") (pin "1") (pinfunction "1_1") (pintype "unspecified"))
      (node (ref "C11") (pin "1") (pinfunction "1_1") (pintype "unspecified"))
      (node (ref "C12") (pin "1") (pinfunction "1_1") (pintype "unspecified"))
      (node (ref "C13") (pin "1") (pinfunction "1_1") (pintype "unspecified"))
      (node (ref "C14") (pin "2") (pinfunction "2_2") (pintype "input"))
      (node (ref "C15") (pin "1") (pinfunction "1_1") (pintype "unspecified"))
      (node (ref "C22") (pin "2") (pinfunction "2_2") (pintype "unspecified"))
      (node (ref "C23") (pin "2") (pinfunction "2_2") (pintype "unspecified"))
      (node (ref "C25") (pin "2") (pinfunction "2_2") (pintype "unspecified"))
      (node (ref "C26") (pin "2") (pinfunction "2_2") (pintype "unspecified"))
      (node (ref "C27") (pin "2") (pinfunction "2_2") (pintype "unspecified"))
      (node (ref "C28") (pin "2") (pinfunction "2_2") (pintype "unspecified"))
      (node (ref "C29") (pin "2") (pinfunction "2_2") (pintype "unspecified"))
      (node (ref "C30") (pin "2") (pinfunction "2_2") (pintype "unspecified"))
      (node (ref "C7") (pin "1") (pinfunction "1_1") (pintype "unspecified"))
      (node (ref "C8") (pin "1") (pinfunction "1_1") (pintype "unspecified"))
      (node (ref "C9") (pin "1") (pinfunction "1_1") (pintype "unspecified"))
      (node (ref "D4") (pin "2") (pinfunction "A_2") (pintype "unspecified"))
      (node (ref "DC1") (pin "2") (pinfunction "2_2") (pintype "unspecified"))
      (node (ref "DC1") (pin "3") (pinfunction "3_3") (pintype "unspecified"))
      (node (ref "H3") (pin "4") (pinfunction "4_4") (pintype "unspecified"))
      (node (ref "H4") (pin "4") (pinfunction "4_4") (pintype "unspecified"))
      (node (ref "NO1") (pin "1") (pinfunction "GND/ADJ_1") (pintype "unspecified"))
      (node (ref "NO2") (pin "1") (pinfunction "GND/ADJ_1") (pintype "unspecified"))
      (node (ref "Q1") (pin "3") (pinfunction "E_3") (pintype "unspecified"))
      (node (ref "R18") (pin "1") (pinfunction "1_1") (pintype "unspecified"))
      (node (ref "R21") (pin "2") (pinfunction "2_2") (pintype "unspecified"))
      (node (ref "R22") (pin "2") (pinfunction "2_2") (pintype "unspecified"))
      (node (ref "R51") (pin "2") (pinfunction "2_2") (pintype "unspecified"))
      (node (ref "R52") (pin "2") (pinfunction "2_2") (pintype "unspecified"))
      (node (ref "R54") (pin "2") (pinfunction "2_2") (pintype "unspecified"))
      (node (ref "R56") (pin "2") (pinfunction "2_2") (pintype "unspecified"))
      (node (ref "R58") (pin "2") (pinfunction "2_2") (pintype "unspecified"))
      (node (ref "R59") (pin "2") (pinfunction "2_2") (pintype "unspecified"))
      (node (ref "U1") (pin "5") (pinfunction "GND_5") (pintype "unspecified"))
      (node (ref "U14") (pin "1") (pinfunction "1_1") (pintype "unspecified"))
      (node (ref "U15") (pin "2") (pinfunction "2_2") (pintype "unspecified"))
      (node (ref "U16") (pin "11") (pinfunction "SD_11") (pintype "unspecified"))
      (node (ref "U16") (pin "13") (pinfunction "VSS_13") (pintype "unspecified"))
      (node (ref "U16") (pin "2") (pinfunction "COM_2") (pintype "unspecified"))
      (node (ref "U17") (pin "23") (pinfunction "VSS_1_23") (pintype "unspecified"))
      (node (ref "U17") (pin "35") (pinfunction "VSS_2_35") (pintype "unspecified"))
      (node (ref "U17") (pin "47") (pinfunction "VSS_3_47") (pintype "unspecified"))
      (node (ref "U17") (pin "8") (pinfunction "VSSA_8") (pintype "unspecified"))
      (node (ref "U18") (pin "4") (pinfunction "GND1_4") (pintype "unspecified"))
      (node (ref "U19") (pin "7") (pinfunction "VSS_7") (pintype "unspecified"))
      (node (ref "U2") (pin "11") (pinfunction "COML_11") (pintype "unspecified"))
      (node (ref "U2") (pin "20") (pinfunction "COMH_20") (pintype "unspecified"))
      (node (ref "U20") (pin "7") (pinfunction "VSS_7") (pintype "unspecified"))
      (node (ref "U21") (pin "11") (pinfunction "VCC-_11") (pintype "unspecified"))
      (node (ref "U23") (pin "11") (pinfunction "VCC-_11") (pintype "unspecified"))
      (node (ref "U24") (pin "4") (pinfunction "GND1_4") (pintype "unspecified"))
      (node (ref "U3") (pin "5") (pinfunction "GND_5") (pintype "unspecified"))
      (node (ref "U4") (pin "5") (pinfunction "GND_5") (pintype "unspecified"))
      (node (ref "U5") (pin "5") (pinfunction "GND_5") (pintype "unspecified"))
    )
    (net (code "14") (name "GUH") (class "Default")
      (node (ref "R25") (pin "2") (pinfunction "2_2") (pintype "unspecified"))
      (node (ref "R6") (pin "1") (pinfunction "1_1") (pintype "unspecified"))
    )
    (net (code "15") (name "GUL") (class "Default")
      (node (ref "R28") (pin "2") (pinfunction "2_2") (pintype "unspecified"))
      (node (ref "R7") (pin "1") (pinfunction "1_1") (pintype "unspecified"))
    )
    (net (code "16") (name "GVH") (class "Default")
      (node (ref "R24") (pin "2") (pinfunction "2_2") (pintype "unspecified"))
      (node (ref "R5") (pin "1") (pinfunction "1_1") (pintype "unspecified"))
    )
    (net (code "17") (name "GVL") (class "Default")
      (node (ref "R27") (pin "2") (pinfunction "2_2") (pintype "unspecified"))
      (node (ref "R8") (pin "1") (pinfunction "1_1") (pintype "unspecified"))
    )
    (net (code "18") (name "GWH") (class "Default")
      (node (ref "R23") (pin "2") (pinfunction "2_2") (pintype "unspecified"))
      (node (ref "R4") (pin "1") (pinfunction "1_1") (pintype "unspecified"))
    )
    (net (code "19") (name "GWL") (class "Default")
      (node (ref "R26") (pin "2") (pinfunction "2_2") (pintype "unspecified"))
      (node (ref "R9") (pin "1") (pinfunction "1_1") (pintype "unspecified"))
    )
    (net (code "20") (name "I2C_SCL") (class "Default")
      (node (ref "U17") (pin "42") (pinfunction "PB6_42") (pintype "unspecified"))
      (node (ref "U24") (pin "3") (pinfunction "SCL1_3") (pintype "unspecified"))
    )
    (net (code "21") (name "I2C_SDA") (class "Default")
      (node (ref "U17") (pin "43") (pinfunction "PB7_43") (pintype "unspecified"))
      (node (ref "U24") (pin "2") (pinfunction "SDA1_2") (pintype "unspecified"))
    )
    (net (code "22") (name "IN1") (class "Default")
      (node (ref "H2") (pin "10") (pinfunction "10_10") (pintype "unspecified"))
      (node (ref "R10") (pin "1") (pinfunction "1_1") (pintype "unspecified"))
    )
    (net (code "23") (name "IN2") (class "Default")
      (node (ref "H2") (pin "9") (pinfunction "9_9") (pintype "unspecified"))
      (node (ref "R11") (pin "1") (pinfunction "1_1") (pintype "unspecified"))
    )
    (net (code "24") (name "IN3") (class "Default")
      (node (ref "H2") (pin "8") (pinfunction "8_8") (pintype "unspecified"))
      (node (ref "R12") (pin "1") (pinfunction "1_1") (pintype "unspecified"))
    )
    (net (code "25") (name "IN4") (class "Default")
      (node (ref "H2") (pin "7") (pinfunction "7_7") (pintype "unspecified"))
      (node (ref "R13") (pin "1") (pinfunction "1_1") (pintype "unspecified"))
    )
    (net (code "26") (name "IN5") (class "Default")
      (node (ref "H2") (pin "6") (pinfunction "6_6") (pintype "unspecified"))
      (node (ref "R14") (pin "1") (pinfunction "1_1") (pintype "unspecified"))
    )
    (net (code "27") (name "IN6") (class "Default")
      (node (ref "H2") (pin "5") (pinfunction "5_5") (pintype "unspecified"))
      (node (ref "R15") (pin "1") (pinfunction "1_1") (pintype "unspecified"))
    )
    (net (code "28") (name "IN7") (class "Default")
      (node (ref "H2") (pin "4") (pinfunction "4_4") (pintype "unspecified"))
      (node (ref "R16") (pin "1") (pinfunction "1_1") (pintype "unspecified"))
    )
    (net (code "29") (name "IN8") (class "Default")
      (node (ref "H2") (pin "3") (pinfunction "3_3") (pintype "unspecified"))
      (node (ref "R17") (pin "1") (pinfunction "1_1") (pintype "unspecified"))
    )
    (net (code "30") (name "INU") (class "Default")
      (node (ref "H6") (pin "3") (pinfunction "3_3") (pintype "unspecified"))
      (node (ref "U8") (pin "7") (pinfunction "VIOUT_7") (pintype "unspecified"))
    )
    (net (code "31") (name "INUH") (class "Default")
      (node (ref "C9") (pin "2") (pinfunction "2_2") (pintype "unspecified"))
      (node (ref "R6") (pin "2") (pinfunction "2_2") (pintype "unspecified"))
      (node (ref "U2") (pin "19") (pinfunction "INUH_19") (pintype "unspecified"))
    )
    (net (code "32") (name "INUL") (class "Default")
      (node (ref "C10") (pin "2") (pinfunction "2_2") (pintype "unspecified"))
      (node (ref "R7") (pin "2") (pinfunction "2_2") (pintype "unspecified"))
      (node (ref "U2") (pin "12") (pinfunction "INLU_12") (pintype "unspecified"))
    )
    (net (code "33") (name "INV") (class "Default")
      (node (ref "H6") (pin "4") (pinfunction "4_4") (pintype "unspecified"))
      (node (ref "U7") (pin "7") (pinfunction "VIOUT_7") (pintype "unspecified"))
    )
    (net (code "34") (name "INVH") (class "Default")
      (node (ref "C8") (pin "2") (pinfunction "2_2") (pintype "unspecified"))
      (node (ref "R5") (pin "2") (pinfunction "2_2") (pintype "unspecified"))
      (node (ref "U2") (pin "25") (pinfunction "INVH_25") (pintype "unspecified"))
    )
    (net (code "35") (name "INVL") (class "Default")
      (node (ref "C11") (pin "2") (pinfunction "2_2") (pintype "unspecified"))
      (node (ref "R8") (pin "2") (pinfunction "2_2") (pintype "unspecified"))
      (node (ref "U2") (pin "13") (pinfunction "INVL_13") (pintype "unspecified"))
    )
    (net (code "36") (name "INW") (class "Default")
      (node (ref "H6") (pin "5") (pinfunction "5_5") (pintype "unspecified"))
      (node (ref "U6") (pin "7") (pinfunction "VIOUT_7") (pintype "unspecified"))
    )
    (net (code "37") (name "INWH") (class "Default")
      (node (ref "C7") (pin "2") (pinfunction "2_2") (pintype "unspecified"))
      (node (ref "R4") (pin "2") (pinfunction "2_2") (pintype "unspecified"))
      (node (ref "U2") (pin "30") (pinfunction "INWH_30") (pintype "unspecified"))
    )
    (net (code "38") (name "INWL") (class "Default")
      (node (ref "C12") (pin "2") (pinfunction "2_2") (pintype "unspecified"))
      (node (ref "R9") (pin "2") (pinfunction "2_2") (pintype "unspecified"))
      (node (ref "U2") (pin "14") (pinfunction "INWL_14") (pintype "unspecified"))
    )
    (net (code "39") (name "IU") (class "Default")
      (node (ref "H6") (pin "6") (pinfunction "6_6") (pintype "unspecified"))
      (node (ref "U9") (pin "7") (pinfunction "VIOUT_7") (pintype "unspecified"))
    )
    (net (code "40") (name "IV") (class "Default")
      (node (ref "H6") (pin "7") (pinfunction "7_7") (pintype "unspecified"))
      (node (ref "U10") (pin "7") (pinfunction "VIOUT_7") (pintype "unspecified"))
    )
    (net (code "41") (name "IW") (class "Default")
      (node (ref "H6") (pin "8") (pinfunction "8_8") (pintype "unspecified"))
      (node (ref "U11") (pin "7") (pinfunction "VIOUT_7") (pintype "unspecified"))
    )
    (net (code "42") (name "N") (class "Default")
      (node (ref "C34") (pin "2") (pinfunction "2_2") (pintype "unspecified"))
      (node (ref "C35") (pin "2") (pinfunction "2_2") (pintype "unspecified"))
      (node (ref "U13") (pin "2") (pinfunction "2_2") (pintype "unspecified"))
      (node (ref "U6") (pin "3") (pinfunction "IP-_3") (pintype "unspecified"))
      (node (ref "U6") (pin "4") (pinfunction "IP-_4") (pintype "unspecified"))
      (node (ref "U7") (pin "3") (pinfunction "IP-_3") (pintype "unspecified"))
      (node (ref "U7") (pin "4") (pinfunction "IP-_4") (pintype "unspecified"))
      (node (ref "U8") (pin "3") (pinfunction "IP-_3") (pintype "unspecified"))
      (node (ref "U8") (pin "4") (pinfunction "IP-_4") (pintype "unspecified"))
    )
    (net (code "43") (name "NRST") (class "Default")
      (node (ref "U17") (pin "7") (pinfunction "NRST_7") (pintype "unspecified"))
    )
    (net (code "44") (name "NU") (class "Default")
      (node (ref "U2") (pin "7") (pinfunction "NU_7") (pintype "unspecified"))
      (node (ref "U8") (pin "1") (pinfunction "IP+_1") (pintype "unspecified"))
      (node (ref "U8") (pin "2") (pinfunction "IP+_2") (pintype "unspecified"))
    )
    (net (code "45") (name "NV") (class "Default")
      (node (ref "U2") (pin "6") (pinfunction "NV_6") (pintype "unspecified"))
      (node (ref "U7") (pin "1") (pinfunction "IP+_1") (pintype "unspecified"))
      (node (ref "U7") (pin "2") (pinfunction "IP+_2") (pintype "unspecified"))
    )
    (net (code "46") (name "NW") (class "Default")
      (node (ref "U2") (pin "5") (pinfunction "NW_5") (pintype "unspecified"))
      (node (ref "U6") (pin "1") (pinfunction "IP+_1") (pintype "unspecified"))
      (node (ref "U6") (pin "2") (pinfunction "IP+_2") (pintype "unspecified"))
    )
    (net (code "47") (name "Net-(D5-C)") (class "Default")
      (node (ref "C24") (pin "1") (pinfunction "1_1") (pintype "input"))
      (node (ref "D5") (pin "1") (pinfunction "C_1") (pintype "unspecified"))
      (node (ref "U16") (pin "6") (pinfunction "VB_6") (pintype "unspecified"))
    )
    (net (code "48") (name "Net-(D6-C)") (class "Default")
      (node (ref "D6") (pin "1") (pinfunction "C_1") (pintype "unspecified"))
      (node (ref "R19") (pin "1") (pinfunction "1_1") (pintype "unspecified"))
      (node (ref "U16") (pin "1") (pinfunction "LO_1") (pintype "unspecified"))
    )
    (net (code "49") (name "Net-(D7-C)") (class "Default")
      (node (ref "D7") (pin "1") (pinfunction "C_1") (pintype "unspecified"))
      (node (ref "R20") (pin "1") (pinfunction "1_1") (pintype "unspecified"))
      (node (ref "U16") (pin "7") (pinfunction "HO_7") (pintype "unspecified"))
    )
    (net (code "50") (name "Net-(LED1-A)") (class "Default")
      (node (ref "LED1") (pin "2") (pinfunction "A_2") (pintype "unspecified"))
      (node (ref "U17") (pin "2") (pinfunction "PC13-TAMPER-RTC_2") (pintype "unspecified"))
    )
    (net (code "51") (name "Net-(LED1-K)") (class "Default")
      (node (ref "LED1") (pin "1") (pinfunction "K_1") (pintype "unspecified"))
      (node (ref "R21") (pin "1") (pinfunction "1_1") (pintype "unspecified"))
    )
    (net (code "52") (name "Net-(LED2-K)") (class "Default")
      (node (ref "LED2") (pin "1") (pinfunction "K_1") (pintype "unspecified"))
      (node (ref "R56") (pin "1") (pinfunction "1_1") (pintype "unspecified"))
    )
    (net (code "53") (name "Net-(Q1-C)") (class "Default")
      (node (ref "L1") (pin "2") (pinfunction "2_2") (pintype "unspecified"))
      (node (ref "Q1") (pin "2") (pinfunction "C_2") (pintype "unspecified"))
      (node (ref "Q2") (pin "3") (pinfunction "E_3") (pintype "unspecified"))
    )
    (net (code "54") (name "Net-(Q2-C)") (class "Default")
      (node (ref "C23") (pin "1") (pinfunction "1_1") (pintype "unspecified"))
      (node (ref "Q2") (pin "2") (pinfunction "C_2") (pintype "unspecified"))
      (node (ref "U14") (pin "2") (pinfunction "2_2") (pintype "unspecified"))
    )
    (net (code "55") (name "Net-(R29-Pad1)") (class "Default")
      (node (ref "R29") (pin "1") (pinfunction "1_1") (pintype "unspecified"))
      (node (ref "R31") (pin "2") (pinfunction "2_2") (pintype "unspecified"))
      (node (ref "R32") (pin "2") (pinfunction "2_2") (pintype "unspecified"))
    )
    (net (code "56") (name "Net-(R30-Pad1)") (class "Default")
      (node (ref "R30") (pin "1") (pinfunction "1_1") (pintype "unspecified"))
      (node (ref "R31") (pin "1") (pinfunction "1_1") (pintype "unspecified"))
      (node (ref "R33") (pin "2") (pinfunction "2_2") (pintype "unspecified"))
    )
    (net (code "57") (name "Net-(R38-Pad2)") (class "Default")
      (node (ref "R38") (pin "2") (pinfunction "2_2") (pintype "unspecified"))
      (node (ref "R40") (pin "1") (pinfunction "1_1") (pintype "unspecified"))
      (node (ref "R41") (pin "1") (pinfunction "1_1") (pintype "unspecified"))
    )
    (net (code "58") (name "Net-(R39-Pad2)") (class "Default")
      (node (ref "R39") (pin "2") (pinfunction "2_2") (pintype "unspecified"))
      (node (ref "R40") (pin "2") (pinfunction "2_2") (pintype "unspecified"))
      (node (ref "R42") (pin "1") (pinfunction "1_1") (pintype "unspecified"))
    )
    (net (code "59") (name "Net-(R45-Pad2)") (class "Default")
      (node (ref "R45") (pin "2") (pinfunction "2_2") (pintype "unspecified"))
      (node (ref "R47") (pin "1") (pinfunction "1_1") (pintype "unspecified"))
      (node (ref "R48") (pin "1") (pinfunction "1_1") (pintype "unspecified"))
    )
    (net (code "60") (name "Net-(R46-Pad2)") (class "Default")
      (node (ref "R46") (pin "2") (pinfunction "2_2") (pintype "unspecified"))
      (node (ref "R47") (pin "2") (pinfunction "2_2") (pintype "unspecified"))
      (node (ref "R49") (pin "1") (pinfunction "1_1") (pintype "unspecified"))
    )
    (net (code "61") (name "Net-(U1-A1)") (class "Default")
      (node (ref "R10") (pin "2") (pinfunction "2_2") (pintype "unspecified"))
      (node (ref "U1") (pin "1") (pinfunction "A1_1") (pintype "unspecified"))
    )
    (net (code "62") (name "Net-(U1-A2)") (class "Default")
      (node (ref "R11") (pin "2") (pinfunction "2_2") (pintype "unspecified"))
      (node (ref "U1") (pin "4") (pinfunction "A2_4") (pintype "unspecified"))
    )
    (net (code "63") (name "Net-(U3-A1)") (class "Default")
      (node (ref "R12") (pin "2") (pinfunction "2_2") (pintype "unspecified"))
      (node (ref "U3") (pin "1") (pinfunction "A1_1") (pintype "unspecified"))
    )
    (net (code "64") (name "Net-(U3-A2)") (class "Default")
      (node (ref "R13") (pin "2") (pinfunction "2_2") (pintype "unspecified"))
      (node (ref "U3") (pin "4") (pinfunction "A2_4") (pintype "unspecified"))
    )
    (net (code "65") (name "Net-(U4-A1)") (class "Default")
      (node (ref "R14") (pin "2") (pinfunction "2_2") (pintype "unspecified"))
      (node (ref "U4") (pin "1") (pinfunction "A1_1") (pintype "unspecified"))
    )
    (net (code "66") (name "Net-(U4-A2)") (class "Default")
      (node (ref "R15") (pin "2") (pinfunction "2_2") (pintype "unspecified"))
      (node (ref "U4") (pin "4") (pinfunction "A2_4") (pintype "unspecified"))
    )
    (net (code "67") (name "Net-(U5-A1)") (class "Default")
      (node (ref "R16") (pin "2") (pinfunction "2_2") (pintype "unspecified"))
      (node (ref "U5") (pin "1") (pinfunction "A1_1") (pintype "unspecified"))
    )
    (net (code "68") (name "Net-(U5-A2)") (class "Default")
      (node (ref "R17") (pin "2") (pinfunction "2_2") (pintype "unspecified"))
      (node (ref "U5") (pin "4") (pinfunction "A2_4") (pintype "unspecified"))
    )
    (net (code "69") (name "Net-(U6-FILTER)") (class "Default")
      (node (ref "C16") (pin "2") (pinfunction "2_2") (pintype "unspecified"))
      (node (ref "U6") (pin "6") (pinfunction "FILTER_6") (pintype "unspecified"))
    )
    (net (code "70") (name "Net-(U7-FILTER)") (class "Default")
      (node (ref "C17") (pin "2") (pinfunction "2_2") (pintype "unspecified"))
      (node (ref "U7") (pin "6") (pinfunction "FILTER_6") (pintype "unspecified"))
    )
    (net (code "71") (name "Net-(U8-FILTER)") (class "Default")
      (node (ref "C18") (pin "2") (pinfunction "2_2") (pintype "unspecified"))
      (node (ref "U8") (pin "6") (pinfunction "FILTER_6") (pintype "unspecified"))
    )
    (net (code "72") (name "Net-(U9-FILTER)") (class "Default")
      (node (ref "C19") (pin "2") (pinfunction "2_2") (pintype "unspecified"))
      (node (ref "U9") (pin "6") (pinfunction "FILTER_6") (pintype "unspecified"))
    )
    (net (code "73") (name "Net-(U10-FILTER)") (class "Default")
      (node (ref "C20") (pin "2") (pinfunction "2_2") (pintype "unspecified"))
      (node (ref "U10") (pin "6") (pinfunction "FILTER_6") (pintype "unspecified"))
    )
    (net (code "74") (name "Net-(U11-FILTER)") (class "Default")
      (node (ref "C21") (pin "2") (pinfunction "2_2") (pintype "unspecified"))
      (node (ref "U11") (pin "6") (pinfunction "FILTER_6") (pintype "unspecified"))
    )
    (net (code "75") (name "Net-(U16-VS)") (class "Default")
      (node (ref "C24") (pin "2") (pinfunction "2_2") (pintype "input"))
      (node (ref "U16") (pin "5") (pinfunction "VS_5") (pintype "unspecified"))
    )
    (net (code "76") (name "Net-(U18-GND2)") (class "Default")
      (node (ref "H1") (pin "4") (pinfunction "4_4") (pintype "unspecified"))
      (node (ref "U18") (pin "5") (pinfunction "GND2_5") (pintype "unspecified"))
    )
    (net (code "77") (name "Net-(U18-SCL2)") (class "Default")
      (node (ref "H1") (pin "3") (pinfunction "3_3") (pintype "unspecified"))
      (node (ref "U18") (pin "6") (pinfunction "SCL2_6") (pintype "unspecified"))
    )
    (net (code "78") (name "Net-(U18-SDA2)") (class "Default")
      (node (ref "H1") (pin "2") (pinfunction "2_2") (pintype "unspecified"))
      (node (ref "U18") (pin "7") (pinfunction "SDA2_7") (pintype "unspecified"))
    )
    (net (code "79") (name "Net-(U18-VCC2)") (class "Default")
      (node (ref "H1") (pin "1") (pinfunction "1_1") (pintype "unspecified"))
      (node (ref "U18") (pin "8") (pinfunction "VCC2_8") (pintype "unspecified"))
    )
    (net (code "80") (name "Net-(U23-NEG{slash}4)") (class "Default")
      (node (ref "U23") (pin "13") (pinfunction "NEG/4_13") (pintype "unspecified"))
      (node (ref "U23") (pin "14") (pinfunction "OUT4_14") (pintype "unspecified"))
    )
    (net (code "81") (name "Net-(U24-GND2)") (class "Default")
      (node (ref "H5") (pin "4") (pinfunction "4_4") (pintype "unspecified"))
      (node (ref "U24") (pin "5") (pinfunction "GND2_5") (pintype "unspecified"))
    )
    (net (code "82") (name "Net-(U24-SCL2)") (class "Default")
      (node (ref "H5") (pin "3") (pinfunction "3_3") (pintype "unspecified"))
      (node (ref "U24") (pin "6") (pinfunction "SCL2_6") (pintype "unspecified"))
    )
    (net (code "83") (name "Net-(U24-SDA2)") (class "Default")
      (node (ref "H5") (pin "2") (pinfunction "2_2") (pintype "unspecified"))
      (node (ref "U24") (pin "7") (pinfunction "SDA2_7") (pintype "unspecified"))
    )
    (net (code "84") (name "Net-(U24-VCC2)") (class "Default")
      (node (ref "H5") (pin "1") (pinfunction "1_1") (pintype "unspecified"))
      (node (ref "U24") (pin "8") (pinfunction "VCC2_8") (pintype "unspecified"))
    )
    (net (code "85") (name "OSC32_in") (class "Default")
      (node (ref "U17") (pin "3") (pinfunction "PC14-OSC32_IN_3") (pintype "unspecified"))
    )
    (net (code "86") (name "OSC32_out") (class "Default")
      (node (ref "U17") (pin "4") (pinfunction "PC15-OSC32_OUT_4") (pintype "unspecified"))
    )
    (net (code "87") (name "OSC_in") (class "Default")
      (node (ref "U17") (pin "5") (pinfunction "PD0-OSC_IN_5") (pintype "unspecified"))
    )
    (net (code "88") (name "OSC_out") (class "Default")
      (node (ref "U17") (pin "6") (pinfunction "PD1-OSC_OUT_6") (pintype "unspecified"))
    )
    (net (code "89") (name "OUT1") (class "Default")
      (node (ref "U1") (pin "7") (pinfunction "VO1_7") (pintype "unspecified"))
      (node (ref "U19") (pin "1") (pinfunction "1A_1") (pintype "unspecified"))
    )
    (net (code "90") (name "OUT2") (class "Default")
      (node (ref "U1") (pin "6") (pinfunction "VO2_6") (pintype "unspecified"))
      (node (ref "U19") (pin "3") (pinfunction "2A_3") (pintype "unspecified"))
    )
    (net (code "91") (name "OUT3") (class "Default")
      (node (ref "U19") (pin "5") (pinfunction "3A_5") (pintype "unspecified"))
      (node (ref "U3") (pin "7") (pinfunction "VO1_7") (pintype "unspecified"))
    )
    (net (code "92") (name "OUT4") (class "Default")
      (node (ref "U19") (pin "13") (pinfunction "6A_13") (pintype "unspecified"))
      (node (ref "U3") (pin "6") (pinfunction "VO2_6") (pintype "unspecified"))
    )
    (net (code "93") (name "OUT5") (class "Default")
      (node (ref "U19") (pin "11") (pinfunction "5A_11") (pintype "unspecified"))
      (node (ref "U4") (pin "7") (pinfunction "VO1_7") (pintype "unspecified"))
    )
    (net (code "94") (name "OUT6") (class "Default")
      (node (ref "U19") (pin "9") (pinfunction "4A_9") (pintype "unspecified"))
      (node (ref "U4") (pin "6") (pinfunction "VO2_6") (pintype "unspecified"))
    )
    (net (code "95") (name "OUT7") (class "Default")
      (node (ref "U20") (pin "1") (pinfunction "1A_1") (pintype "unspecified"))
      (node (ref "U5") (pin "7") (pinfunction "VO1_7") (pintype "unspecified"))
    )
    (net (code "96") (name "OUT8") (class "Default")
      (node (ref "U20") (pin "3") (pinfunction "2A_3") (pintype "unspecified"))
      (node (ref "U5") (pin "6") (pinfunction "VO2_6") (pintype "unspecified"))
    )
    (net (code "97") (name "P") (class "Default")
      (node (ref "C34") (pin "1") (pinfunction "1_1") (pintype "unspecified"))
      (node (ref "C35") (pin "1") (pinfunction "1_1") (pintype "unspecified"))
      (node (ref "U13") (pin "1") (pinfunction "1_1") (pintype "unspecified"))
      (node (ref "U2") (pin "1") (pinfunction "P_1") (pintype "unspecified"))
    )
    (net (code "98") (name "PGND") (class "Default")
      (node (ref "C31") (pin "1") (pinfunction "1_1") (pintype "unspecified"))
      (node (ref "C32") (pin "1") (pinfunction "1_1") (pintype "unspecified"))
      (node (ref "C33") (pin "1") (pinfunction "1_1") (pintype "unspecified"))
      (node (ref "R30") (pin "2") (pinfunction "2_2") (pintype "unspecified"))
      (node (ref "R41") (pin "2") (pinfunction "2_2") (pintype "unspecified"))
      (node (ref "R48") (pin "2") (pinfunction "2_2") (pintype "unspecified"))
    )
    (net (code "99") (name "RSC") (class "Default")
      (node (ref "U2") (pin "18") (pinfunction "RSC_18") (pintype "unspecified"))
    )
    (net (code "100") (name "RTH") (class "Default")
      (node (ref "R18") (pin "2") (pinfunction "2_2") (pintype "unspecified"))
      (node (ref "U2") (pin "8") (pinfunction "RTH_8") (pintype "unspecified"))
    )
    (net (code "101") (name "RX0") (class "Default")
      (node (ref "H3") (pin "2") (pinfunction "2_2") (pintype "unspecified"))
      (node (ref "U17") (pin "31") (pinfunction "PA10_31") (pintype "unspecified"))
    )
    (net (code "102") (name "SCL") (class "Default")
      (node (ref "U17") (pin "45") (pinfunction "PB8_45") (pintype "unspecified"))
      (node (ref "U18") (pin "3") (pinfunction "SCL1_3") (pintype "unspecified"))
    )
    (net (code "103") (name "SDA") (class "Default")
      (node (ref "U17") (pin "46") (pinfunction "PB9_46") (pintype "unspecified"))
      (node (ref "U18") (pin "2") (pinfunction "SDA1_2") (pintype "unspecified"))
    )
    (net (code "104") (name "SPI_MISO") (class "Default")
      (node (ref "U17") (pin "27") (pinfunction "PB14_27") (pintype "unspecified"))
    )
    (net (code "105") (name "SPI_MOSI") (class "Default")
      (node (ref "U17") (pin "28") (pinfunction "PB15_28") (pintype "unspecified"))
    )
    (net (code "106") (name "SPI_NSS") (class "Default")
      (node (ref "U17") (pin "25") (pinfunction "PB12_25") (pintype "unspecified"))
    )
    (net (code "107") (name "SPI_SCK") (class "Default")
      (node (ref "U17") (pin "26") (pinfunction "PB13_26") (pintype "unspecified"))
    )
    (net (code "108") (name "SWCLK") (class "Default")
      (node (ref "H4") (pin "2") (pinfunction "2_2") (pintype "unspecified"))
      (node (ref "U17") (pin "37") (pinfunction "PA14_37") (pintype "unspecified"))
    )
    (net (code "109") (name "SWDIO") (class "Default")
      (node (ref "H4") (pin "3") (pinfunction "3_3") (pintype "unspecified"))
      (node (ref "U17") (pin "34") (pinfunction "PA13_34") (pintype "unspecified"))
    )
    (net (code "110") (name "T1") (class "Default")
      (node (ref "D6") (pin "2") (pinfunction "A_2") (pintype "unspecified"))
      (node (ref "Q1") (pin "1") (pinfunction "G_1") (pintype "unspecified"))
      (node (ref "R19") (pin "2") (pinfunction "2_2") (pintype "unspecified"))
    )
    (net (code "111") (name "T2") (class "Default")
      (node (ref "D7") (pin "2") (pinfunction "A_2") (pintype "unspecified"))
      (node (ref "Q2") (pin "1") (pinfunction "G_1") (pintype "unspecified"))
      (node (ref "R20") (pin "2") (pinfunction "2_2") (pintype "unspecified"))
    )
    (net (code "112") (name "TX0") (class "Default")
      (node (ref "H3") (pin "3") (pinfunction "3_3") (pintype "unspecified"))
      (node (ref "U17") (pin "30") (pinfunction "PA9_30") (pintype "unspecified"))
    )
    (net (code "113") (name "U") (class "Default")
      (node (ref "U2") (pin "4") (pinfunction "U_4") (pintype "unspecified"))
      (node (ref "U9") (pin "1") (pinfunction "IP+_1") (pintype "unspecified"))
      (node (ref "U9") (pin "2") (pinfunction "IP+_2") (pintype "unspecified"))
    )
    (net (code "114") (name "U_") (class "Default")
      (node (ref "L2") (pin "1") (pinfunction "1_1") (pintype "unspecified"))
      (node (ref "U12") (pin "3") (pinfunction "3_3") (pintype "unspecified"))
      (node (ref "U9") (pin "3") (pinfunction "IP-_3") (pintype "unspecified"))
      (node (ref "U9") (pin "4") (pinfunction "IP-_4") (pintype "unspecified"))
    )
    (net (code "115") (name "V") (class "Default")
      (node (ref "U10") (pin "1") (pinfunction "IP+_1") (pintype "unspecified"))
      (node (ref "U10") (pin "2") (pinfunction "IP+_2") (pintype "unspecified"))
      (node (ref "U2") (pin "3") (pinfunction "V_3") (pintype "unspecified"))
    )
    (net (code "116") (name "VBDU") (class "Default")
      (node (ref "R3") (pin "2") (pinfunction "2_2") (pintype "unspecified"))
      (node (ref "U2") (pin "22") (pinfunction "VBDU_22") (pintype "unspecified"))
    )
    (net (code "117") (name "VBDV") (class "Default")
      (node (ref "R2") (pin "2") (pinfunction "2_2") (pintype "unspecified"))
      (node (ref "U2") (pin "27") (pinfunction "VBDV_27") (pintype "unspecified"))
    )
    (net (code "118") (name "VBDW") (class "Default")
      (node (ref "R1") (pin "2") (pinfunction "2_2") (pintype "unspecified"))
      (node (ref "U2") (pin "32") (pinfunction "VBDW_32") (pintype "unspecified"))
    )
    (net (code "119") (name "VBU") (class "Default")
      (node (ref "C5") (pin "2") (pinfunction "2_2") (pintype "unspecified"))
      (node (ref "C6") (pin "1") (pinfunction "1_1") (pintype "input"))
      (node (ref "D3") (pin "1") (pinfunction "K_1") (pintype "unspecified"))
      (node (ref "U2") (pin "23") (pinfunction "VBU_23") (pintype "unspecified"))
    )
    (net (code "120") (name "VBV") (class "Default")
      (node (ref "C3") (pin "2") (pinfunction "2_2") (pintype "unspecified"))
      (node (ref "C4") (pin "1") (pinfunction "1_1") (pintype "input"))
      (node (ref "D2") (pin "1") (pinfunction "K_1") (pintype "unspecified"))
      (node (ref "U2") (pin "28") (pinfunction "VBV_28") (pintype "unspecified"))
    )
    (net (code "121") (name "VBW") (class "Default")
      (node (ref "C1") (pin "1") (pinfunction "1_1") (pintype "input"))
      (node (ref "C2") (pin "2") (pinfunction "2_2") (pintype "unspecified"))
      (node (ref "D1") (pin "1") (pinfunction "K_1") (pintype "unspecified"))
      (node (ref "U2") (pin "33") (pinfunction "VBW_33") (pintype "unspecified"))
    )
    (net (code "122") (name "VFO") (class "Default")
      (node (ref "U2") (pin "15") (pinfunction "VFO_15") (pintype "unspecified"))
    )
    (net (code "123") (name "VSU") (class "Default")
      (node (ref "C5") (pin "1") (pinfunction "1_1") (pintype "unspecified"))
      (node (ref "C6") (pin "2") (pinfunction "2_2") (pintype "input"))
      (node (ref "D3") (pin "2") (pinfunction "A_2") (pintype "unspecified"))
      (node (ref "U2") (pin "24") (pinfunction "VSU_24") (pintype "unspecified"))
    )
    (net (code "124") (name "VSV") (class "Default")
      (node (ref "C3") (pin "1") (pinfunction "1_1") (pintype "unspecified"))
      (node (ref "C4") (pin "2") (pinfunction "2_2") (pintype "input"))
      (node (ref "D2") (pin "2") (pinfunction "A_2") (pintype "unspecified"))
      (node (ref "U2") (pin "29") (pinfunction "VSV_29") (pintype "unspecified"))
    )
    (net (code "125") (name "VSW") (class "Default")
      (node (ref "C1") (pin "2") (pinfunction "2_2") (pintype "input"))
      (node (ref "C2") (pin "1") (pinfunction "1_1") (pintype "unspecified"))
      (node (ref "D1") (pin "2") (pinfunction "A_2") (pintype "unspecified"))
      (node (ref "U2") (pin "34") (pinfunction "VSW_34") (pintype "unspecified"))
    )
    (net (code "126") (name "V_") (class "Default")
      (node (ref "L3") (pin "1") (pinfunction "1_1") (pintype "unspecified"))
      (node (ref "U10") (pin "3") (pinfunction "IP-_3") (pintype "unspecified"))
      (node (ref "U10") (pin "4") (pinfunction "IP-_4") (pintype "unspecified"))
      (node (ref "U12") (pin "2") (pinfunction "2_2") (pintype "unspecified"))
    )
    (net (code "127") (name "Va") (class "Default")
      (node (ref "R50") (pin "1") (pinfunction "1_1") (pintype "unspecified"))
      (node (ref "U23") (pin "1") (pinfunction "OUT1_1") (pintype "unspecified"))
      (node (ref "U23") (pin "2") (pinfunction "NEG/1_2") (pintype "unspecified"))
    )
    (net (code "128") (name "Vb") (class "Default")
      (node (ref "R53") (pin "1") (pinfunction "1_1") (pintype "unspecified"))
      (node (ref "U23") (pin "6") (pinfunction "NEG/2_6") (pintype "unspecified"))
      (node (ref "U23") (pin "7") (pinfunction "OUT2_7") (pintype "unspecified"))
    )
    (net (code "129") (name "Vbb") (class "Default")
      (node (ref "R59") (pin "1") (pinfunction "1_1") (pintype "unspecified"))
      (node (ref "R60") (pin "2") (pinfunction "2_2") (pintype "unspecified"))
      (node (ref "U17") (pin "13") (pinfunction "PA3_13") (pintype "unspecified"))
    )
    (net (code "130") (name "Vc") (class "Default")
      (node (ref "R55") (pin "1") (pinfunction "1_1") (pintype "unspecified"))
      (node (ref "U23") (pin "8") (pinfunction "OUT3_8") (pintype "unspecified"))
      (node (ref "U23") (pin "9") (pinfunction "NEG3_9") (pintype "unspecified"))
    )
    (net (code "131") (name "W") (class "Default")
      (node (ref "U11") (pin "1") (pinfunction "IP+_1") (pintype "unspecified"))
      (node (ref "U11") (pin "2") (pinfunction "IP+_2") (pintype "unspecified"))
      (node (ref "U2") (pin "2") (pinfunction "W_2") (pintype "unspecified"))
    )
    (net (code "132") (name "W_") (class "Default")
      (node (ref "L4") (pin "1") (pinfunction "1_1") (pintype "unspecified"))
      (node (ref "U11") (pin "3") (pinfunction "IP-_3") (pintype "unspecified"))
      (node (ref "U11") (pin "4") (pinfunction "IP-_4") (pintype "unspecified"))
      (node (ref "U12") (pin "1") (pinfunction "1_1") (pintype "unspecified"))
    )
    (net (code "133") (name "_5V") (class "Default")
      (node (ref "H2") (pin "1") (pinfunction "1_1") (pintype "unspecified"))
      (node (ref "H6") (pin "2") (pinfunction "2_2") (pintype "unspecified"))
      (node (ref "U10") (pin "8") (pinfunction "VCC_8") (pintype "unspecified"))
      (node (ref "U11") (pin "8") (pinfunction "VCC_8") (pintype "unspecified"))
      (node (ref "U6") (pin "8") (pinfunction "VCC_8") (pintype "unspecified"))
      (node (ref "U7") (pin "8") (pinfunction "VCC_8") (pintype "unspecified"))
      (node (ref "U8") (pin "8") (pinfunction "VCC_8") (pintype "unspecified"))
      (node (ref "U9") (pin "8") (pinfunction "VCC_8") (pintype "unspecified"))
    )
    (net (code "134") (name "_OUT1") (class "Default")
      (node (ref "R23") (pin "1") (pinfunction "1_1") (pintype "unspecified"))
      (node (ref "U19") (pin "2") (pinfunction "1Y_2") (pintype "unspecified"))
    )
    (net (code "135") (name "_OUT2") (class "Default")
      (node (ref "R24") (pin "1") (pinfunction "1_1") (pintype "unspecified"))
      (node (ref "U19") (pin "4") (pinfunction "2Y_4") (pintype "unspecified"))
    )
    (net (code "136") (name "_OUT3") (class "Default")
      (node (ref "R25") (pin "1") (pinfunction "1_1") (pintype "unspecified"))
      (node (ref "U19") (pin "6") (pinfunction "3Y_6") (pintype "unspecified"))
    )
    (net (code "137") (name "_OUT4") (class "Default")
      (node (ref "R26") (pin "1") (pinfunction "1_1") (pintype "unspecified"))
      (node (ref "U19") (pin "12") (pinfunction "6Y_12") (pintype "unspecified"))
    )
    (net (code "138") (name "_OUT5") (class "Default")
      (node (ref "R27") (pin "1") (pinfunction "1_1") (pintype "unspecified"))
      (node (ref "U19") (pin "10") (pinfunction "5Y_10") (pintype "unspecified"))
    )
    (net (code "139") (name "_OUT6") (class "Default")
      (node (ref "R28") (pin "1") (pinfunction "1_1") (pintype "unspecified"))
      (node (ref "U19") (pin "8") (pinfunction "4Y_8") (pintype "unspecified"))
    )
    (net (code "140") (name "_OUT7") (class "Default")
      (node (ref "U16") (pin "12") (pinfunction "LIN_12") (pintype "unspecified"))
      (node (ref "U20") (pin "2") (pinfunction "1Y_2") (pintype "unspecified"))
    )
    (net (code "141") (name "_OUT8") (class "Default")
      (node (ref "U16") (pin "10") (pinfunction "HIN_10") (pintype "unspecified"))
      (node (ref "U20") (pin "4") (pinfunction "2Y_4") (pintype "unspecified"))
    )
    (net (code "142") (name "_U_") (class "Default")
      (node (ref "C33") (pin "2") (pinfunction "2_2") (pintype "unspecified"))
      (node (ref "L2") (pin "2") (pinfunction "2_2") (pintype "unspecified"))
      (node (ref "R29") (pin "2") (pinfunction "2_2") (pintype "unspecified"))
      (node (ref "U22") (pin "3") (pinfunction "3_3") (pintype "unspecified"))
    )
    (net (code "143") (name "_V_") (class "Default")
      (node (ref "C32") (pin "2") (pinfunction "2_2") (pintype "unspecified"))
      (node (ref "L3") (pin "2") (pinfunction "2_2") (pintype "unspecified"))
      (node (ref "R42") (pin "2") (pinfunction "2_2") (pintype "unspecified"))
      (node (ref "U22") (pin "2") (pinfunction "2_2") (pintype "unspecified"))
    )
    (net (code "144") (name "_Va") (class "Default")
      (node (ref "R50") (pin "2") (pinfunction "2_2") (pintype "unspecified"))
      (node (ref "R51") (pin "1") (pinfunction "1_1") (pintype "unspecified"))
      (node (ref "U17") (pin "10") (pinfunction "PA0-WKUP_10") (pintype "unspecified"))
    )
    (net (code "145") (name "_Vb") (class "Default")
      (node (ref "R52") (pin "1") (pinfunction "1_1") (pintype "unspecified"))
      (node (ref "R53") (pin "2") (pinfunction "2_2") (pintype "unspecified"))
      (node (ref "U17") (pin "11") (pinfunction "PA1_11") (pintype "unspecified"))
    )
    (net (code "146") (name "_Vc") (class "Default")
      (node (ref "R54") (pin "1") (pinfunction "1_1") (pintype "unspecified"))
      (node (ref "R55") (pin "2") (pinfunction "2_2") (pintype "unspecified"))
      (node (ref "U17") (pin "12") (pinfunction "PA2_12") (pintype "unspecified"))
    )
    (net (code "147") (name "_W_") (class "Default")
      (node (ref "C31") (pin "2") (pinfunction "2_2") (pintype "unspecified"))
      (node (ref "L4") (pin "2") (pinfunction "2_2") (pintype "unspecified"))
      (node (ref "R49") (pin "2") (pinfunction "2_2") (pintype "unspecified"))
      (node (ref "U22") (pin "1") (pinfunction "1_1") (pintype "unspecified"))
    )
    (net (code "148") (name "aop_out1") (class "Default")
      (node (ref "R34") (pin "1") (pinfunction "1_1") (pintype "unspecified"))
      (node (ref "U21") (pin "1") (pinfunction "OUT1_1") (pintype "unspecified"))
      (node (ref "U23") (pin "3") (pinfunction "POS/1_3") (pintype "unspecified"))
    )
    (net (code "149") (name "aop_out2") (class "Default")
      (node (ref "R37") (pin "1") (pinfunction "1_1") (pintype "unspecified"))
      (node (ref "U21") (pin "7") (pinfunction "OUT2_7") (pintype "unspecified"))
      (node (ref "U23") (pin "5") (pinfunction "POS/2_5") (pintype "unspecified"))
    )
    (net (code "150") (name "aop_out3") (class "Default")
      (node (ref "R44") (pin "1") (pinfunction "1_1") (pintype "unspecified"))
      (node (ref "U21") (pin "8") (pinfunction "OUT3_8") (pintype "unspecified"))
      (node (ref "U23") (pin "10") (pinfunction "POS/3_10") (pintype "unspecified"))
    )
    (net (code "151") (name "aop_out4") (class "Default")
      (node (ref "R35") (pin "1") (pinfunction "1_1") (pintype "unspecified"))
      (node (ref "R36") (pin "1") (pinfunction "1_1") (pintype "unspecified"))
      (node (ref "R43") (pin "1") (pinfunction "1_1") (pintype "unspecified"))
      (node (ref "U21") (pin "13") (pinfunction "NEG/4_13") (pintype "unspecified"))
      (node (ref "U21") (pin "14") (pinfunction "OUT4_14") (pintype "unspecified"))
      (node (ref "U23") (pin "12") (pinfunction "POS/4_12") (pintype "unspecified"))
    )
    (net (code "152") (name "neg1") (class "Default")
      (node (ref "R32") (pin "1") (pinfunction "1_1") (pintype "unspecified"))
      (node (ref "R34") (pin "2") (pinfunction "2_2") (pintype "unspecified"))
      (node (ref "U21") (pin "2") (pinfunction "NEG/1_2") (pintype "unspecified"))
    )
    (net (code "153") (name "neg2") (class "Default")
      (node (ref "R37") (pin "2") (pinfunction "2_2") (pintype "unspecified"))
      (node (ref "R39") (pin "1") (pinfunction "1_1") (pintype "unspecified"))
      (node (ref "U21") (pin "6") (pinfunction "NEG/2_6") (pintype "unspecified"))
    )
    (net (code "154") (name "neg3") (class "Default")
      (node (ref "R44") (pin "2") (pinfunction "2_2") (pintype "unspecified"))
      (node (ref "R46") (pin "1") (pinfunction "1_1") (pintype "unspecified"))
      (node (ref "U21") (pin "9") (pinfunction "NEG3_9") (pintype "unspecified"))
    )
    (net (code "155") (name "pos1") (class "Default")
      (node (ref "R33") (pin "1") (pinfunction "1_1") (pintype "unspecified"))
      (node (ref "R35") (pin "2") (pinfunction "2_2") (pintype "unspecified"))
      (node (ref "U21") (pin "3") (pinfunction "POS/1_3") (pintype "unspecified"))
    )
    (net (code "156") (name "pos2") (class "Default")
      (node (ref "R36") (pin "2") (pinfunction "2_2") (pintype "unspecified"))
      (node (ref "R38") (pin "1") (pinfunction "1_1") (pintype "unspecified"))
      (node (ref "U21") (pin "5") (pinfunction "POS/2_5") (pintype "unspecified"))
    )
    (net (code "157") (name "pos3") (class "Default")
      (node (ref "R43") (pin "2") (pinfunction "2_2") (pintype "unspecified"))
      (node (ref "R45") (pin "1") (pinfunction "1_1") (pintype "unspecified"))
      (node (ref "U21") (pin "10") (pinfunction "POS/3_10") (pintype "unspecified"))
    )
    (net (code "158") (name "pos4") (class "Default")
      (node (ref "R57") (pin "2") (pinfunction "2_2") (pintype "unspecified"))
      (node (ref "R58") (pin "1") (pinfunction "1_1") (pintype "unspecified"))
      (node (ref "U21") (pin "12") (pinfunction "POS/4_12") (pintype "unspecified"))
    )
    (net (code "159") (name "unconnected-(U16-NC-Pad4)") (class "Default")
      (node (ref "U16") (pin "4") (pinfunction "NC_4") (pintype "unspecified"))
    )
    (net (code "160") (name "unconnected-(U16-NC-Pad8)") (class "Default")
      (node (ref "U16") (pin "8") (pinfunction "NC_8") (pintype "unspecified"))
    )
    (net (code "161") (name "unconnected-(U16-NC-Pad14)") (class "Default")
      (node (ref "U16") (pin "14") (pinfunction "NC_14") (pintype "unspecified"))
    )
    (net (code "162") (name "unconnected-(U17-PA4-Pad14)") (class "Default")
      (node (ref "U17") (pin "14") (pinfunction "PA4_14") (pintype "unspecified"))
    )
    (net (code "163") (name "unconnected-(U17-PA5-Pad15)") (class "Default")
      (node (ref "U17") (pin "15") (pinfunction "PA5_15") (pintype "unspecified"))
    )
    (net (code "164") (name "unconnected-(U17-PA6-Pad16)") (class "Default")
      (node (ref "U17") (pin "16") (pinfunction "PA6_16") (pintype "unspecified"))
    )
    (net (code "165") (name "unconnected-(U17-PA7-Pad17)") (class "Default")
      (node (ref "U17") (pin "17") (pinfunction "PA7_17") (pintype "unspecified"))
    )
    (net (code "166") (name "unconnected-(U17-PA8-Pad29)") (class "Default")
      (node (ref "U17") (pin "29") (pinfunction "PA8_29") (pintype "unspecified"))
    )
    (net (code "167") (name "unconnected-(U17-PA11-Pad32)") (class "Default")
      (node (ref "U17") (pin "32") (pinfunction "PA11_32") (pintype "unspecified"))
    )
    (net (code "168") (name "unconnected-(U17-PA12-Pad33)") (class "Default")
      (node (ref "U17") (pin "33") (pinfunction "PA12_33") (pintype "unspecified"))
    )
    (net (code "169") (name "unconnected-(U17-PB0-Pad18)") (class "Default")
      (node (ref "U17") (pin "18") (pinfunction "PB0_18") (pintype "unspecified"))
    )
    (net (code "170") (name "unconnected-(U17-PB1-Pad19)") (class "Default")
      (node (ref "U17") (pin "19") (pinfunction "PB1_19") (pintype "unspecified"))
    )
    (net (code "171") (name "unconnected-(U17-PB2-Pad20)") (class "Default")
      (node (ref "U17") (pin "20") (pinfunction "PB2_20") (pintype "unspecified"))
    )
    (net (code "172") (name "unconnected-(U17-PB10-Pad21)") (class "Default")
      (node (ref "U17") (pin "21") (pinfunction "PB10_21") (pintype "unspecified"))
    )
    (net (code "173") (name "unconnected-(U17-PB11-Pad22)") (class "Default")
      (node (ref "U17") (pin "22") (pinfunction "PB11_22") (pintype "unspecified"))
    )
    (net (code "174") (name "unconnected-(U17-VBAT-Pad1)") (class "Default")
      (node (ref "U17") (pin "1") (pinfunction "VBAT_1") (pintype "unspecified"))
    )
    (net (code "175") (name "unconnected-(U20-3A-Pad5)") (class "Default")
      (node (ref "U20") (pin "5") (pinfunction "3A_5") (pintype "unspecified"))
    )
    (net (code "176") (name "unconnected-(U20-3Y-Pad6)") (class "Default")
      (node (ref "U20") (pin "6") (pinfunction "3Y_6") (pintype "unspecified"))
    )
    (net (code "177") (name "unconnected-(U20-4A-Pad9)") (class "Default")
      (node (ref "U20") (pin "9") (pinfunction "4A_9") (pintype "unspecified"))
    )
    (net (code "178") (name "unconnected-(U20-4Y-Pad8)") (class "Default")
      (node (ref "U20") (pin "8") (pinfunction "4Y_8") (pintype "unspecified"))
    )
    (net (code "179") (name "unconnected-(U20-5A-Pad11)") (class "Default")
      (node (ref "U20") (pin "11") (pinfunction "5A_11") (pintype "unspecified"))
    )
    (net (code "180") (name "unconnected-(U20-5Y-Pad10)") (class "Default")
      (node (ref "U20") (pin "10") (pinfunction "5Y_10") (pintype "unspecified"))
    )
    (net (code "181") (name "unconnected-(U20-6A-Pad13)") (class "Default")
      (node (ref "U20") (pin "13") (pinfunction "6A_13") (pintype "unspecified"))
    )
    (net (code "182") (name "unconnected-(U20-6Y-Pad12)") (class "Default")
      (node (ref "U20") (pin "12") (pinfunction "6Y_12") (pintype "unspecified"))
    )
  )
)
